# MSV-back.net
KiCad netlist of a schematic drawn in EAGLE
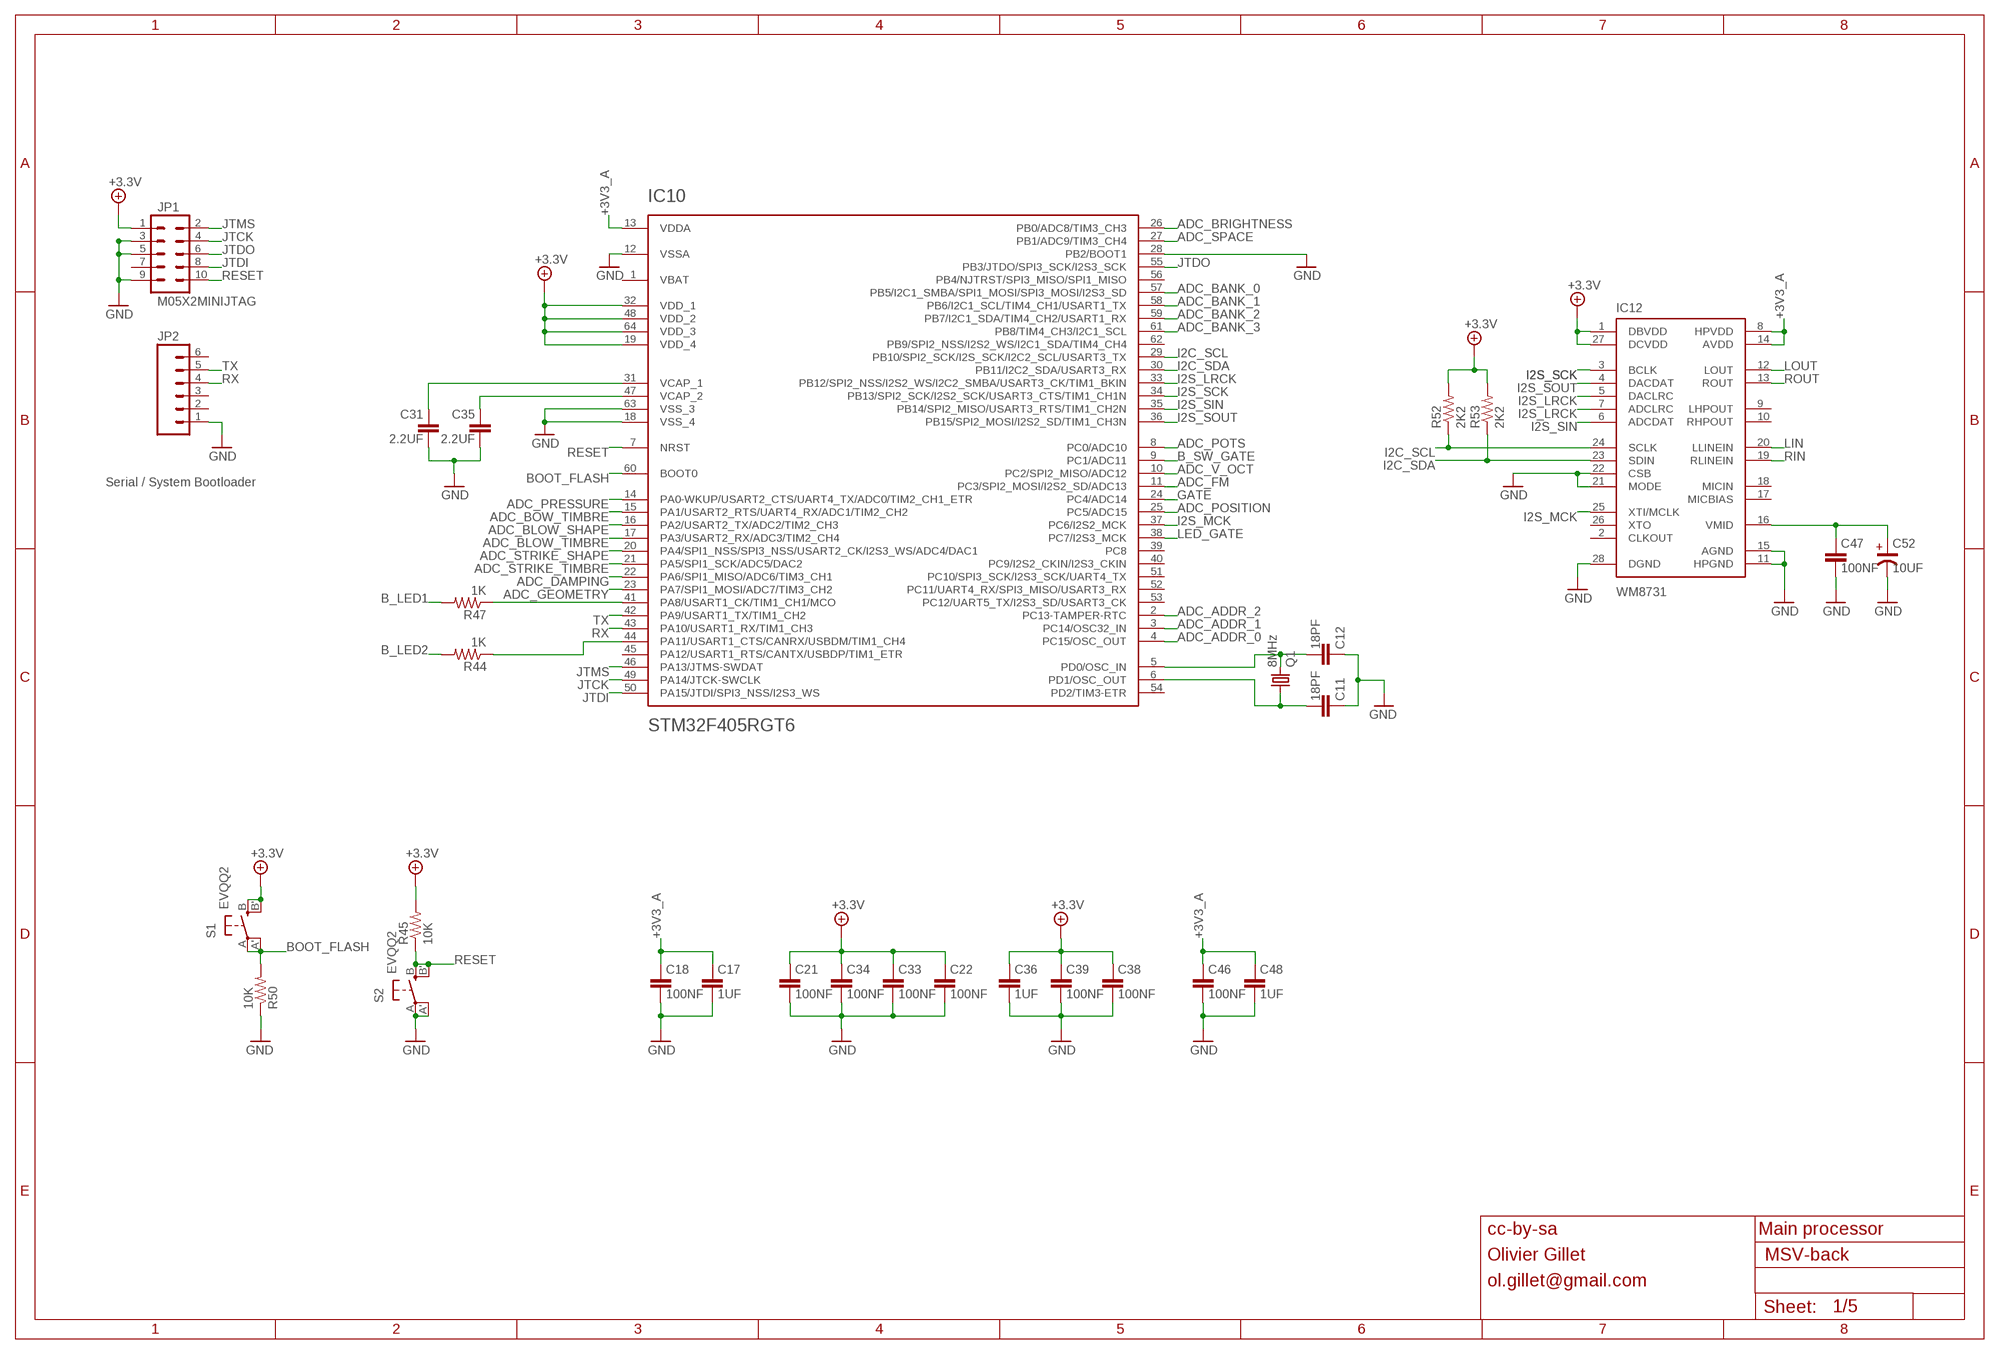
[diagram p0: schematic, sheet 1]
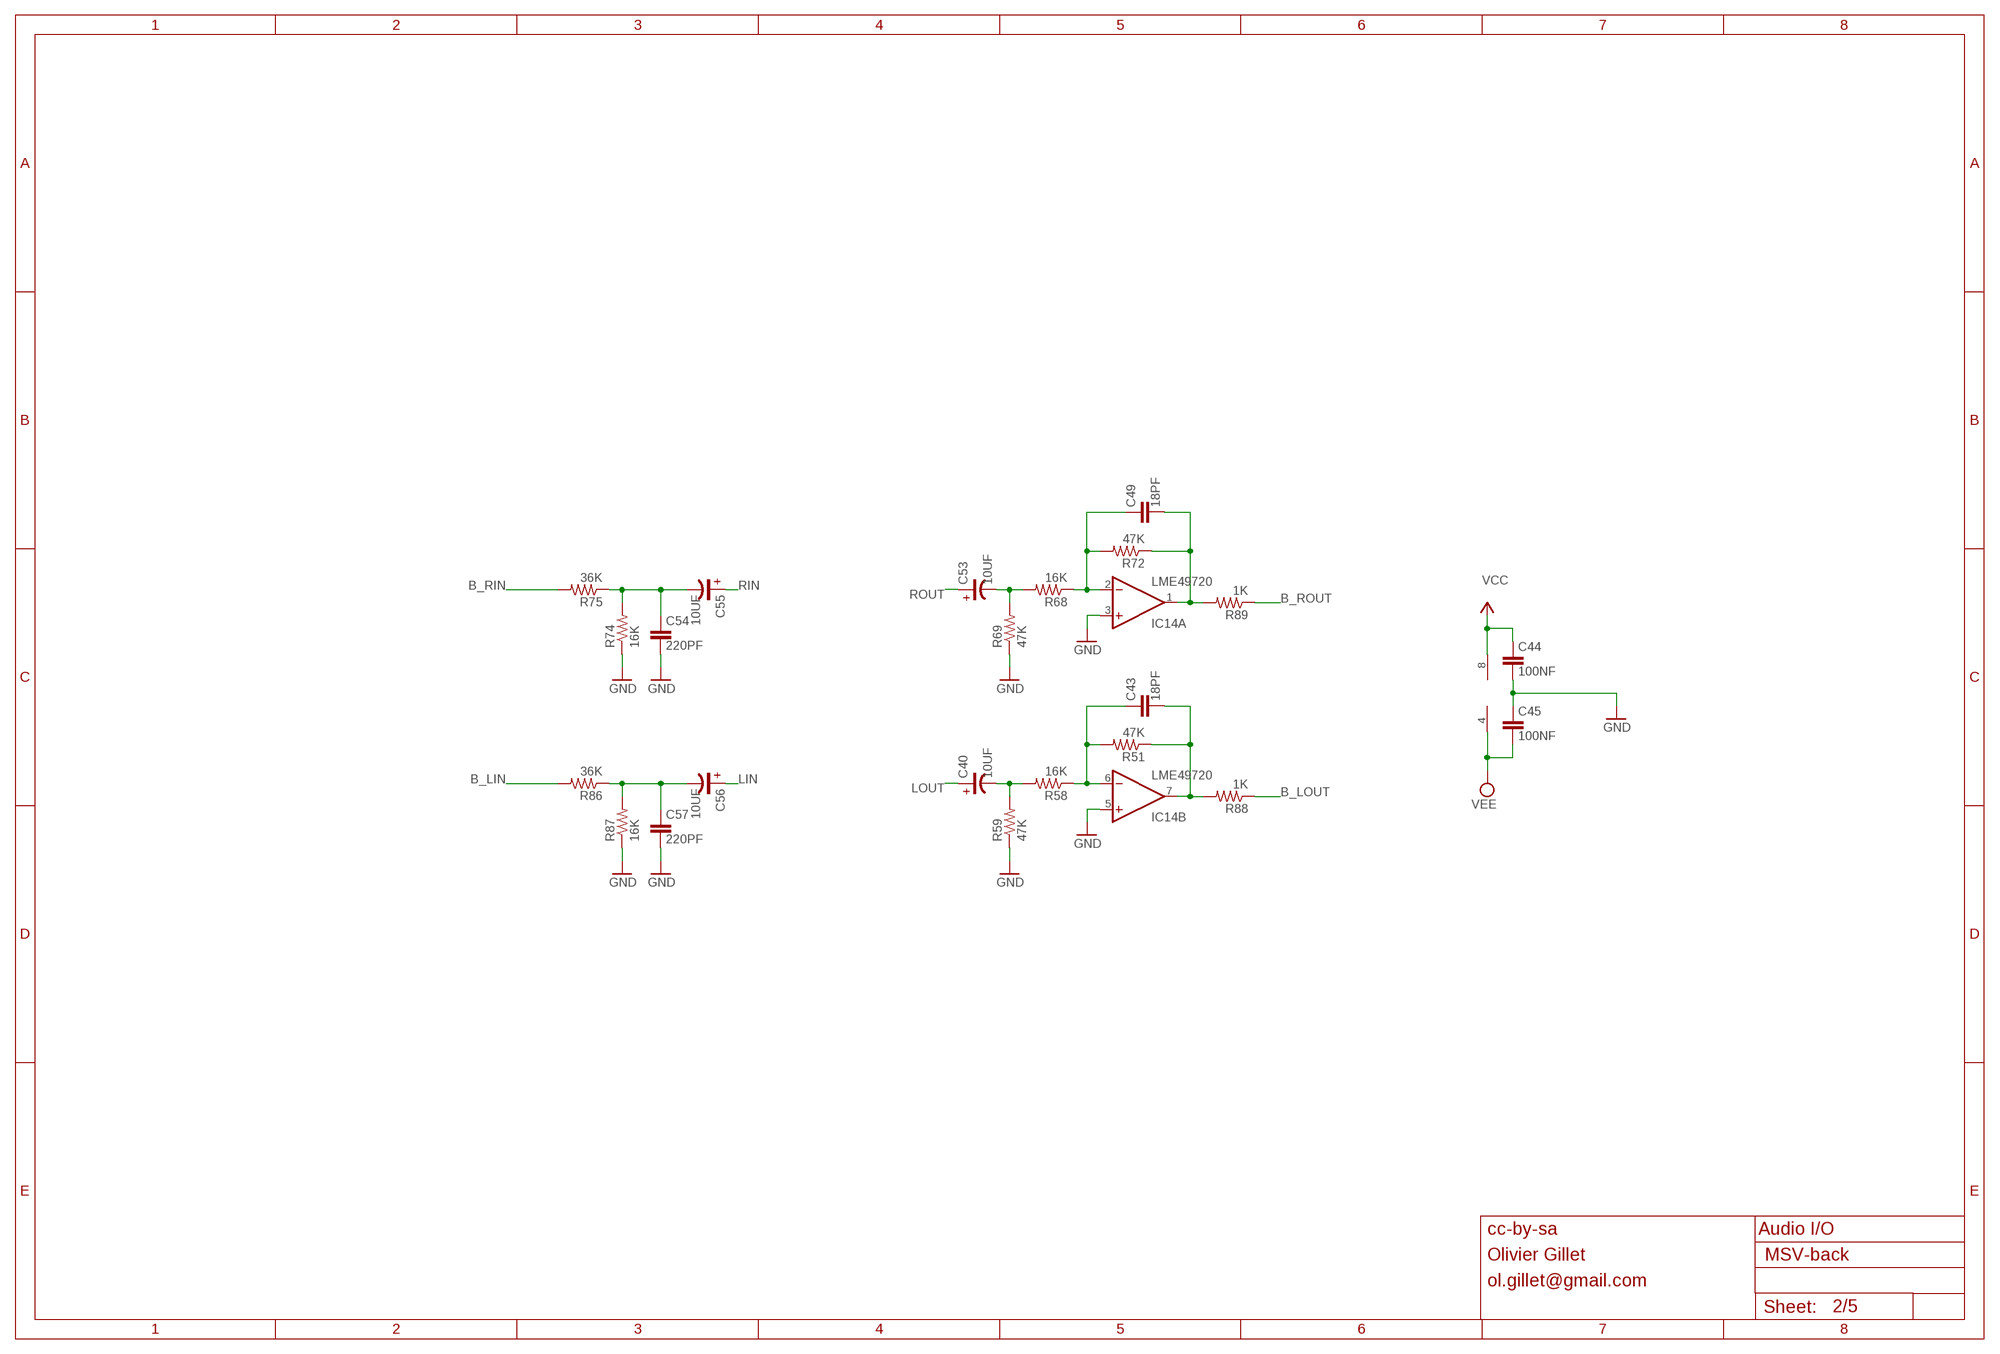
[diagram p1: schematic, sheet 2]
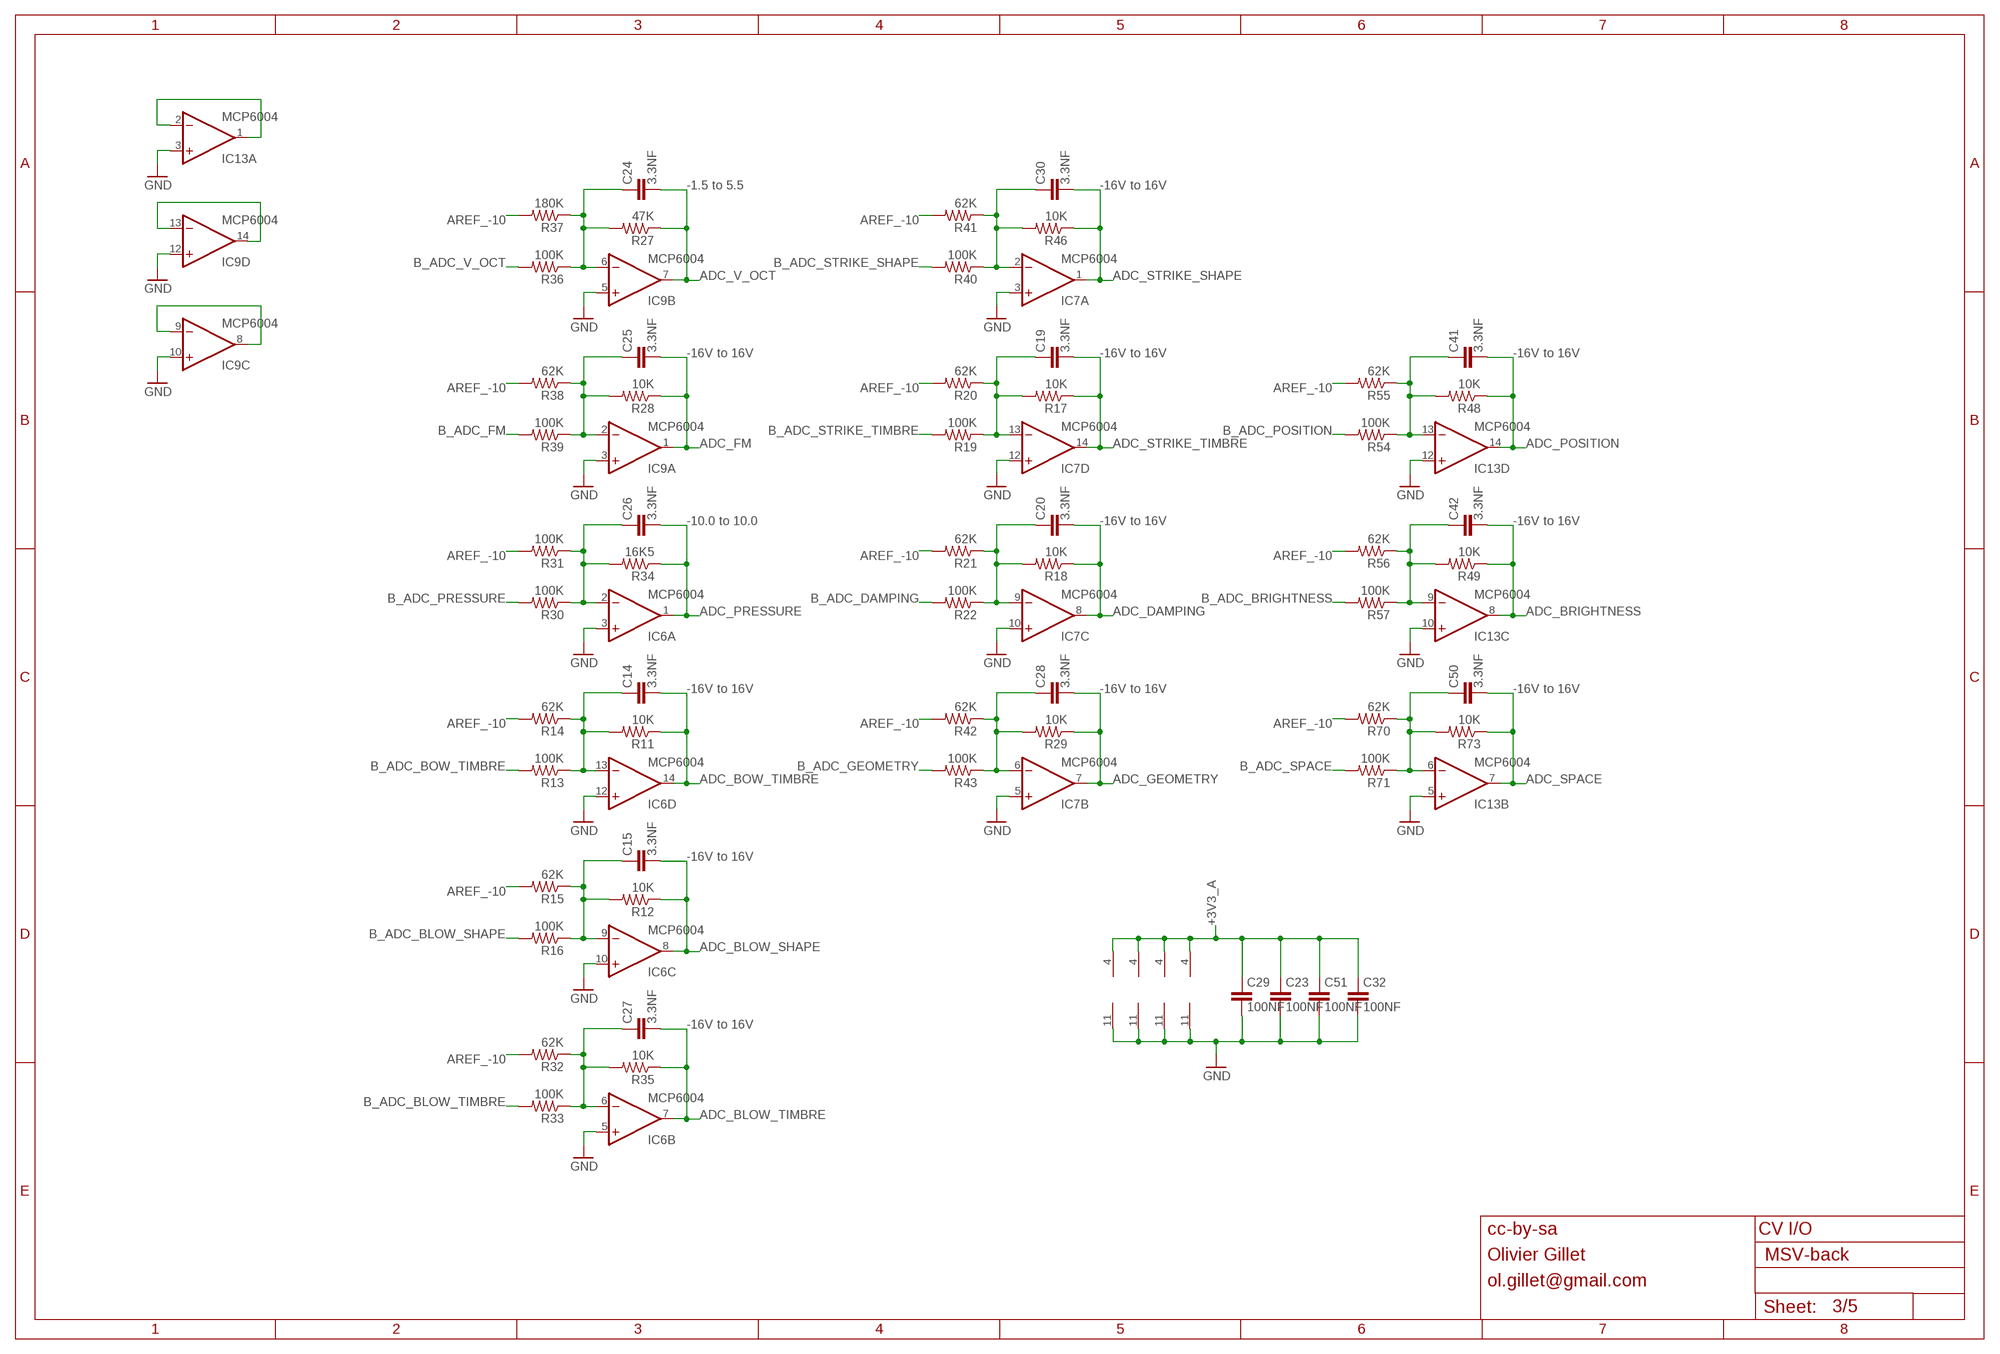
[diagram p2: schematic, sheet 3]
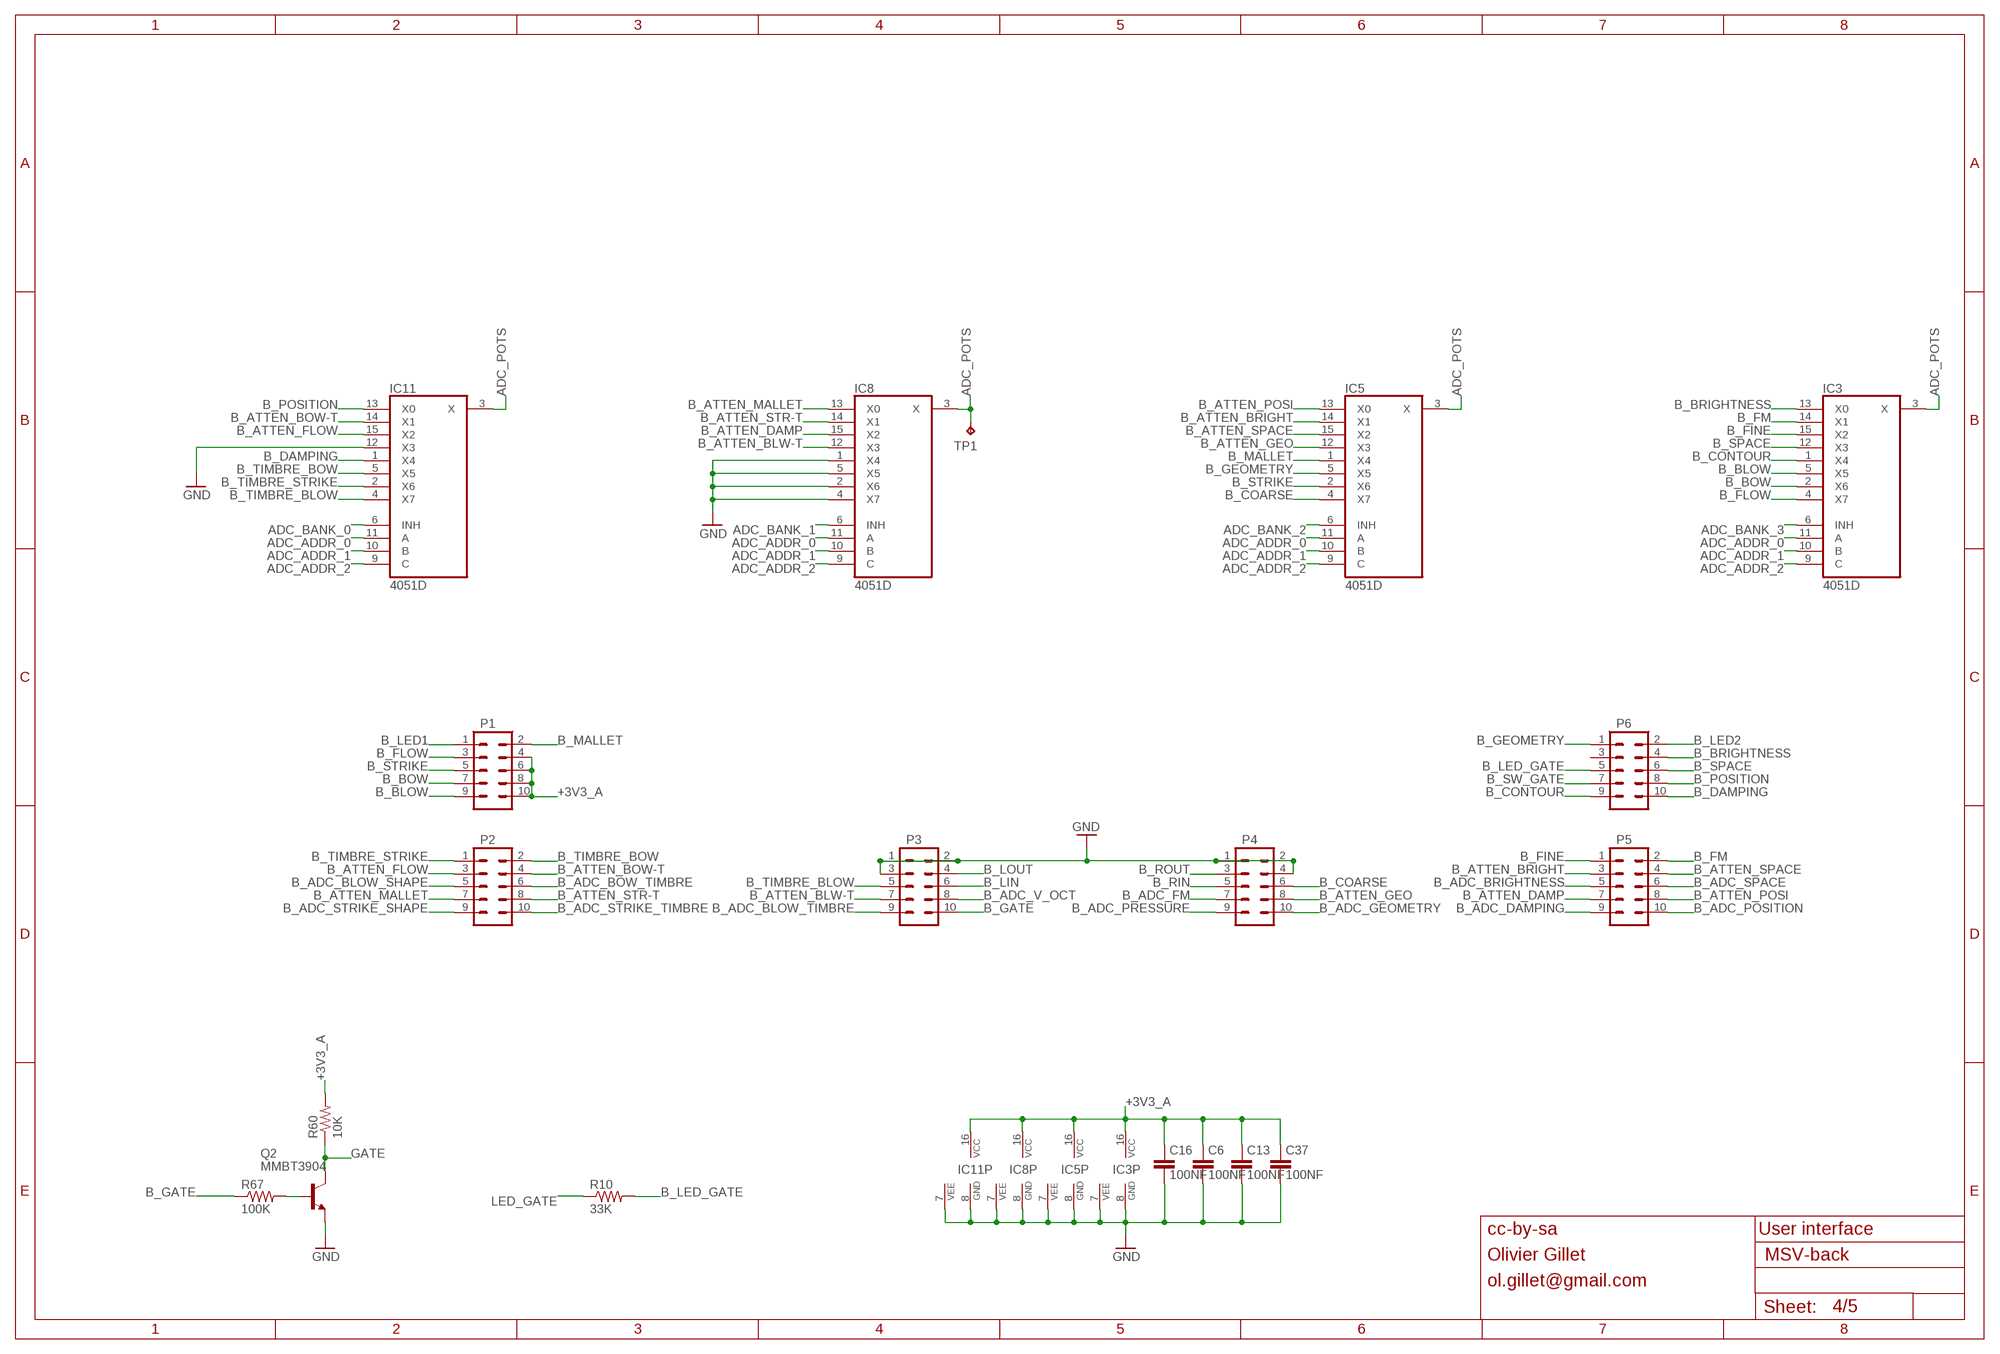
[diagram p3: schematic, sheet 4]
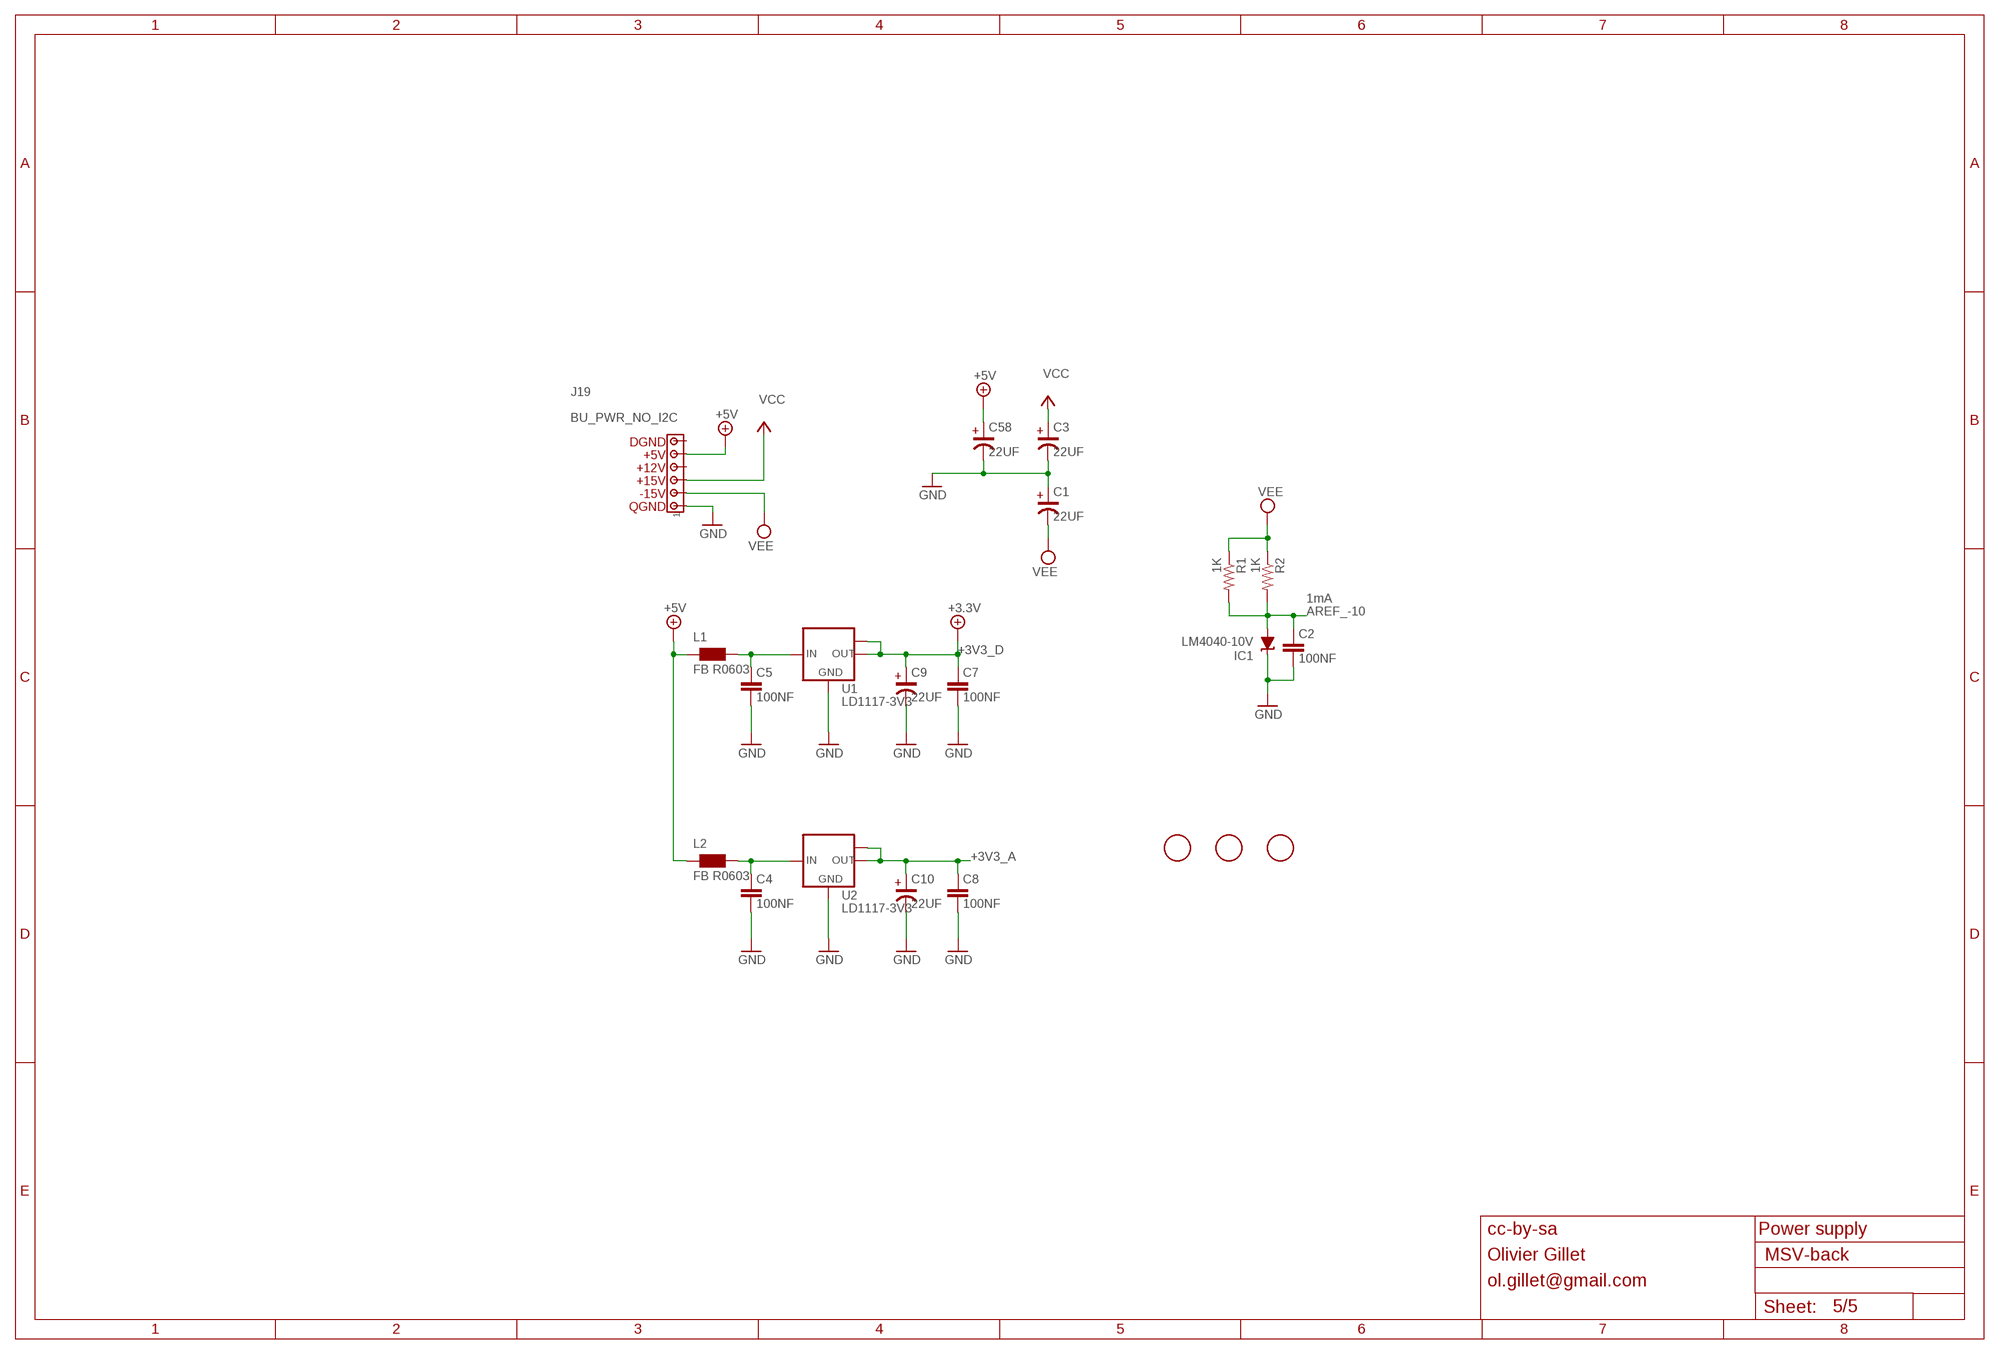
[diagram p4: schematic, sheet 5]

(export (version "E")
  (design (tool "Eeschema 10.0.6"))
  (components
    (comp (ref "C6")
      (value "100NF")
      (footprint "eagle-import:C0603")
      (libsource (lib "eagle-import") (part "C-EUC0603"))
    )
    (comp (ref "C13")
      (value "100NF")
      (footprint "eagle-import:C0603")
      (libsource (lib "eagle-import") (part "C-EUC0603"))
    )
    (comp (ref "C16")
      (value "100NF")
      (footprint "eagle-import:C0603")
      (libsource (lib "eagle-import") (part "C-EUC0603"))
    )
    (comp (ref "C37")
      (value "100NF")
      (footprint "eagle-import:C0603")
      (libsource (lib "eagle-import") (part "C-EUC0603"))
    )
    (comp (ref "IC3")
      (value "4051D")
      (footprint "eagle-import:SO-16")
      (libsource (lib "eagle-import") (part "4051D"))
    )
    (comp (ref "IC5")
      (value "4051D")
      (footprint "eagle-import:SO-16")
      (libsource (lib "eagle-import") (part "4051D"))
    )
    (comp (ref "IC8")
      (value "4051D")
      (footprint "eagle-import:SO-16")
      (libsource (lib "eagle-import") (part "4051D"))
    )
    (comp (ref "IC11")
      (value "4051D")
      (footprint "eagle-import:SO-16")
      (fields (field (name "SPICEPREFIX") "X"))
      (libsource (lib "eagle-import") (part "4051D"))
    )
    (comp (ref "P1")
      (value "M05X2_LOCK_MALE")
      (footprint "eagle-import:2X5_LOCK_MALE")
      (libsource (lib "eagle-import") (part "M05X2_LOCK_MALE"))
    )
    (comp (ref "P2")
      (value "M05X2_LOCK_MALE")
      (footprint "eagle-import:2X5_LOCK_MALE")
      (libsource (lib "eagle-import") (part "M05X2_LOCK_MALE"))
    )
    (comp (ref "P3")
      (value "M05X2_LOCK_MALE")
      (footprint "eagle-import:2X5_LOCK_MALE")
      (libsource (lib "eagle-import") (part "M05X2_LOCK_MALE"))
    )
    (comp (ref "P4")
      (value "M05X2_LOCK_MALE")
      (footprint "eagle-import:2X5_LOCK_MALE")
      (libsource (lib "eagle-import") (part "M05X2_LOCK_MALE"))
    )
    (comp (ref "P5")
      (value "M05X2_LOCK_MALE")
      (footprint "eagle-import:2X5_LOCK_MALE")
      (libsource (lib "eagle-import") (part "M05X2_LOCK_MALE"))
    )
    (comp (ref "P6")
      (value "M05X2_LOCK_MALE")
      (footprint "eagle-import:2X5_LOCK_MALE")
      (libsource (lib "eagle-import") (part "M05X2_LOCK_MALE"))
    )
    (comp (ref "Q2")
      (value "MMBT3904")
      (footprint "eagle-import:SOT23-BEC")
      (libsource (lib "eagle-import") (part "-NPN-SOT23-BECMMBT3904LT1"))
    )
    (comp (ref "R10")
      (value "33K")
      (footprint "eagle-import:R0603")
      (libsource (lib "eagle-import") (part "R-US_R0603"))
    )
    (comp (ref "R60")
      (value "10K")
      (footprint "eagle-import:R0603")
      (libsource (lib "eagle-import") (part "R-US_R0603"))
    )
    (comp (ref "R67")
      (value "100K")
      (footprint "eagle-import:R0603")
      (libsource (lib "eagle-import") (part "R-US_R0603"))
    )
    (comp (ref "TP1")
      (value "TPTP15R")
      (footprint "eagle-import:TP15R")
      (libsource (lib "eagle-import") (part "TPTP15R"))
    )
    (comp (ref "C1")
      (value "22UF")
      (footprint "eagle-import:PANASONIC_C")
      (libsource (lib "eagle-import") (part "C-EU-POL_C"))
    )
    (comp (ref "C2")
      (value "100NF")
      (footprint "eagle-import:C0603")
      (libsource (lib "eagle-import") (part "C-EUC0603"))
    )
    (comp (ref "C3")
      (value "22UF")
      (footprint "eagle-import:PANASONIC_C")
      (libsource (lib "eagle-import") (part "C-EU-POL_C"))
    )
    (comp (ref "C4")
      (value "100NF")
      (footprint "eagle-import:C0603")
      (libsource (lib "eagle-import") (part "C-EUC0603"))
    )
    (comp (ref "C5")
      (value "100NF")
      (footprint "eagle-import:C0603")
      (libsource (lib "eagle-import") (part "C-EUC0603"))
    )
    (comp (ref "C7")
      (value "100NF")
      (footprint "eagle-import:C0603")
      (libsource (lib "eagle-import") (part "C-EUC0603"))
    )
    (comp (ref "C8")
      (value "100NF")
      (footprint "eagle-import:C0603")
      (libsource (lib "eagle-import") (part "C-EUC0603"))
    )
    (comp (ref "C9")
      (value "22UF")
      (footprint "eagle-import:PANASONIC_C")
      (libsource (lib "eagle-import") (part "C-EU-POL_C"))
    )
    (comp (ref "C10")
      (value "22UF")
      (footprint "eagle-import:PANASONIC_C")
      (libsource (lib "eagle-import") (part "C-EU-POL_C"))
    )
    (comp (ref "C58")
      (value "22UF")
      (footprint "eagle-import:PANASONIC_C")
      (libsource (lib "eagle-import") (part "C-EU-POL_C"))
    )
    (comp (ref "FD1")
      (value "FIDUCIAL")
      (footprint "eagle-import:FIDUCIAL_1MM")
      (libsource (lib "eagle-import") (part "FIDUCIAL"))
    )
    (comp (ref "FD2")
      (value "FIDUCIAL")
      (footprint "eagle-import:FIDUCIAL_1MM")
      (libsource (lib "eagle-import") (part "FIDUCIAL"))
    )
    (comp (ref "FD3")
      (value "FIDUCIAL")
      (footprint "eagle-import:FIDUCIAL_1MM")
      (libsource (lib "eagle-import") (part "FIDUCIAL"))
    )
    (comp (ref "IC1")
      (value "LM4040-10V")
      (footprint "eagle-import:DBZ_R-PDSO-G3")
      (fields (field (name "MPN") "LM4041A12IDBZR"))
      (libsource (lib "eagle-import") (part "LM4040-10VDBZA12"))
    )
    (comp (ref "J19")
      (value "BU_PWR_NO_I2C")
      (footprint "eagle-import:MTA_156")
      (libsource (lib "eagle-import") (part "BU_PWR_NO_I2C"))
    )
    (comp (ref "L1")
      (value "FB R0603")
      (footprint "eagle-import:WUERTH-ELEKTRONIK_0603")
      (fields (field (name "MPN") "MI0603J601R-10"))
      (libsource (lib "eagle-import") (part "FERRITE_BEAD_0603"))
    )
    (comp (ref "L2")
      (value "FB R0603")
      (footprint "eagle-import:WUERTH-ELEKTRONIK_0603")
      (fields (field (name "MPN") "MI0603J601R-10"))
      (libsource (lib "eagle-import") (part "FERRITE_BEAD_0603"))
    )
    (comp (ref "R1")
      (value "1K")
      (footprint "eagle-import:R0603")
      (libsource (lib "eagle-import") (part "R-US_R0603"))
    )
    (comp (ref "R2")
      (value "1K")
      (footprint "eagle-import:R0603")
      (libsource (lib "eagle-import") (part "R-US_R0603"))
    )
    (comp (ref "U1")
      (value "LD1117-3V3")
      (footprint "eagle-import:SOT223")
      (fields (field (name "MPN") "LD1117S33CTR"))
      (libsource (lib "eagle-import") (part "LD1117-3V3"))
    )
    (comp (ref "U2")
      (value "LD1117-3V3")
      (footprint "eagle-import:SOT223")
      (fields (field (name "MPN") "LD1117S33CTR"))
      (libsource (lib "eagle-import") (part "LD1117-3V3"))
    )
    (comp (ref "C11")
      (value "18PF")
      (footprint "eagle-import:C0603")
      (libsource (lib "eagle-import") (part "C-EUC0603"))
    )
    (comp (ref "C12")
      (value "18PF")
      (footprint "eagle-import:C0603")
      (libsource (lib "eagle-import") (part "C-EUC0603"))
    )
    (comp (ref "C17")
      (value "1UF")
      (footprint "eagle-import:C0603")
      (libsource (lib "eagle-import") (part "C-EUC0603"))
    )
    (comp (ref "C18")
      (value "100NF")
      (footprint "eagle-import:C0603")
      (libsource (lib "eagle-import") (part "C-EUC0603"))
    )
    (comp (ref "C21")
      (value "100NF")
      (footprint "eagle-import:C0603")
      (libsource (lib "eagle-import") (part "C-EUC0603"))
    )
    (comp (ref "C22")
      (value "100NF")
      (footprint "eagle-import:C0603")
      (libsource (lib "eagle-import") (part "C-EUC0603"))
    )
    (comp (ref "C31")
      (value "2.2UF")
      (footprint "eagle-import:C0603")
      (libsource (lib "eagle-import") (part "C-EUC0603"))
    )
    (comp (ref "C33")
      (value "100NF")
      (footprint "eagle-import:C0603")
      (libsource (lib "eagle-import") (part "C-EUC0603"))
    )
    (comp (ref "C34")
      (value "100NF")
      (footprint "eagle-import:C0603")
      (libsource (lib "eagle-import") (part "C-EUC0603"))
    )
    (comp (ref "C35")
      (value "2.2UF")
      (footprint "eagle-import:C0603")
      (libsource (lib "eagle-import") (part "C-EUC0603"))
    )
    (comp (ref "C36")
      (value "1UF")
      (footprint "eagle-import:C0603")
      (libsource (lib "eagle-import") (part "C-EUC0603"))
    )
    (comp (ref "C38")
      (value "100NF")
      (footprint "eagle-import:C0603")
      (libsource (lib "eagle-import") (part "C-EUC0603"))
    )
    (comp (ref "C39")
      (value "100NF")
      (footprint "eagle-import:C0603")
      (libsource (lib "eagle-import") (part "C-EUC0603"))
    )
    (comp (ref "C46")
      (value "100NF")
      (footprint "eagle-import:C0603")
      (libsource (lib "eagle-import") (part "C-EUC0603"))
    )
    (comp (ref "C47")
      (value "100NF")
      (footprint "eagle-import:C0603")
      (libsource (lib "eagle-import") (part "C-EUC0603"))
    )
    (comp (ref "C48")
      (value "1UF")
      (footprint "eagle-import:C0603")
      (libsource (lib "eagle-import") (part "C-EUC0603"))
    )
    (comp (ref "C52")
      (value "10UF")
      (footprint "eagle-import:PANASONIC_B")
      (libsource (lib "eagle-import") (part "C-EU-POL_B"))
    )
    (comp (ref "IC10")
      (value "STM32F405RGT6")
      (footprint "eagle-import:TQFP-10X10-64")
      (fields (field (name "MPN") "empty"))
      (libsource (lib "eagle-import") (part "STM32F20X"))
    )
    (comp (ref "IC12")
      (value "WM8731")
      (footprint "eagle-import:SSOP-28")
      (fields (field (name "MPN") "WM8731SEDS/RV"))
      (libsource (lib "eagle-import") (part "WM8731"))
    )
    (comp (ref "JP1")
      (value "M05X2MINIJTAG")
      (footprint "eagle-import:2X5-1.27")
      (fields (field (name "MPN") "20021111-00010T4LF"))
      (libsource (lib "eagle-import") (part "M05X2MINIJTAG"))
    )
    (comp (ref "JP2")
      (value "M06_SQUARE")
      (footprint "eagle-import:1X06_SQUARE")
      (libsource (lib "eagle-import") (part "M06_SQUARE"))
    )
    (comp (ref "Q1")
      (value "8MHz")
      (footprint "eagle-import:HC49UP")
      (libsource (lib "eagle-import") (part "CRYSTALHC49UP"))
    )
    (comp (ref "R44")
      (value "1K")
      (footprint "eagle-import:R0603")
      (libsource (lib "eagle-import") (part "R-US_R0603"))
    )
    (comp (ref "R45")
      (value "10K")
      (footprint "eagle-import:R0603")
      (libsource (lib "eagle-import") (part "R-US_R0603"))
    )
    (comp (ref "R47")
      (value "1K")
      (footprint "eagle-import:R0603")
      (libsource (lib "eagle-import") (part "R-US_R0603"))
    )
    (comp (ref "R50")
      (value "10K")
      (footprint "eagle-import:R0603")
      (libsource (lib "eagle-import") (part "R-US_R0603"))
    )
    (comp (ref "R52")
      (value "2K2")
      (footprint "eagle-import:R0603")
      (libsource (lib "eagle-import") (part "R-US_R0603"))
    )
    (comp (ref "R53")
      (value "2K2")
      (footprint "eagle-import:R0603")
      (libsource (lib "eagle-import") (part "R-US_R0603"))
    )
    (comp (ref "S1")
      (value "EVQQ2")
      (footprint "eagle-import:EVQ-Q2")
      (libsource (lib "eagle-import") (part "EVQQ2"))
    )
    (comp (ref "S2")
      (value "EVQQ2")
      (footprint "eagle-import:EVQ-Q2")
      (libsource (lib "eagle-import") (part "EVQQ2"))
    )
    (comp (ref "C40")
      (value "10UF")
      (footprint "eagle-import:PANASONIC_B")
      (libsource (lib "eagle-import") (part "C-EU-POL_B"))
    )
    (comp (ref "C43")
      (value "18PF")
      (footprint "eagle-import:C0603")
      (libsource (lib "eagle-import") (part "C-EUC0603"))
    )
    (comp (ref "C44")
      (value "100NF")
      (footprint "eagle-import:C0603")
      (libsource (lib "eagle-import") (part "C-EUC0603"))
    )
    (comp (ref "C45")
      (value "100NF")
      (footprint "eagle-import:C0603")
      (libsource (lib "eagle-import") (part "C-EUC0603"))
    )
    (comp (ref "C49")
      (value "18PF")
      (footprint "eagle-import:C0603")
      (libsource (lib "eagle-import") (part "C-EUC0603"))
    )
    (comp (ref "C53")
      (value "10UF")
      (footprint "eagle-import:PANASONIC_B")
      (libsource (lib "eagle-import") (part "C-EU-POL_B"))
    )
    (comp (ref "C54")
      (value "220PF")
      (footprint "eagle-import:C0603")
      (libsource (lib "eagle-import") (part "C-EUC0603"))
    )
    (comp (ref "C55")
      (value "10UF")
      (footprint "eagle-import:PANASONIC_B")
      (libsource (lib "eagle-import") (part "C-EU-POL_B"))
    )
    (comp (ref "C56")
      (value "10UF")
      (footprint "eagle-import:PANASONIC_B")
      (libsource (lib "eagle-import") (part "C-EU-POL_B"))
    )
    (comp (ref "C57")
      (value "220PF")
      (footprint "eagle-import:C0603")
      (libsource (lib "eagle-import") (part "C-EUC0603"))
    )
    (comp (ref "IC14")
      (value "LME49720")
      (footprint "eagle-import:TSSOP-8")
      (fields (field (name "MPN") "TL072CPWR"))
      (libsource (lib "eagle-import") (part "TL072_TSSOP-8"))
    )
    (comp (ref "R51")
      (value "47K")
      (footprint "eagle-import:R0603")
      (libsource (lib "eagle-import") (part "R-US_R0603"))
    )
    (comp (ref "R58")
      (value "16K")
      (footprint "eagle-import:R0603")
      (libsource (lib "eagle-import") (part "R-US_R0603"))
    )
    (comp (ref "R59")
      (value "47K")
      (footprint "eagle-import:R0603")
      (libsource (lib "eagle-import") (part "R-US_R0603"))
    )
    (comp (ref "R68")
      (value "16K")
      (footprint "eagle-import:R0603")
      (libsource (lib "eagle-import") (part "R-US_R0603"))
    )
    (comp (ref "R69")
      (value "47K")
      (footprint "eagle-import:R0603")
      (libsource (lib "eagle-import") (part "R-US_R0603"))
    )
    (comp (ref "R72")
      (value "47K")
      (footprint "eagle-import:R0603")
      (libsource (lib "eagle-import") (part "R-US_R0603"))
    )
    (comp (ref "R74")
      (value "16K")
      (footprint "eagle-import:R0603")
      (libsource (lib "eagle-import") (part "R-US_R0603"))
    )
    (comp (ref "R75")
      (value "36K")
      (footprint "eagle-import:R0603")
      (libsource (lib "eagle-import") (part "R-US_R0603"))
    )
    (comp (ref "R86")
      (value "36K")
      (footprint "eagle-import:R0603")
      (libsource (lib "eagle-import") (part "R-US_R0603"))
    )
    (comp (ref "R87")
      (value "16K")
      (footprint "eagle-import:R0603")
      (libsource (lib "eagle-import") (part "R-US_R0603"))
    )
    (comp (ref "R88")
      (value "1K")
      (footprint "eagle-import:R0603")
      (libsource (lib "eagle-import") (part "R-US_R0603"))
    )
    (comp (ref "R89")
      (value "1K")
      (footprint "eagle-import:R0603")
      (libsource (lib "eagle-import") (part "R-US_R0603"))
    )
    (comp (ref "C14")
      (value "3.3NF")
      (footprint "eagle-import:C0603")
      (libsource (lib "eagle-import") (part "C-EUC0603"))
    )
    (comp (ref "C15")
      (value "3.3NF")
      (footprint "eagle-import:C0603")
      (libsource (lib "eagle-import") (part "C-EUC0603"))
    )
    (comp (ref "C19")
      (value "3.3NF")
      (footprint "eagle-import:C0603")
      (libsource (lib "eagle-import") (part "C-EUC0603"))
    )
    (comp (ref "C20")
      (value "3.3NF")
      (footprint "eagle-import:C0603")
      (libsource (lib "eagle-import") (part "C-EUC0603"))
    )
    (comp (ref "C23")
      (value "100NF")
      (footprint "eagle-import:C0603")
      (libsource (lib "eagle-import") (part "C-EUC0603"))
    )
    (comp (ref "C24")
      (value "3.3NF")
      (footprint "eagle-import:C0603")
      (libsource (lib "eagle-import") (part "C-EUC0603"))
    )
    (comp (ref "C25")
      (value "3.3NF")
      (footprint "eagle-import:C0603")
      (libsource (lib "eagle-import") (part "C-EUC0603"))
    )
    (comp (ref "C26")
      (value "3.3NF")
      (footprint "eagle-import:C0603")
      (libsource (lib "eagle-import") (part "C-EUC0603"))
    )
    (comp (ref "C27")
      (value "3.3NF")
      (footprint "eagle-import:C0603")
      (libsource (lib "eagle-import") (part "C-EUC0603"))
    )
    (comp (ref "C28")
      (value "3.3NF")
      (footprint "eagle-import:C0603")
      (libsource (lib "eagle-import") (part "C-EUC0603"))
    )
    (comp (ref "C29")
      (value "100NF")
      (footprint "eagle-import:C0603")
      (libsource (lib "eagle-import") (part "C-EUC0603"))
    )
    (comp (ref "C30")
      (value "3.3NF")
      (footprint "eagle-import:C0603")
      (libsource (lib "eagle-import") (part "C-EUC0603"))
    )
    (comp (ref "C32")
      (value "100NF")
      (footprint "eagle-import:C0603")
      (libsource (lib "eagle-import") (part "C-EUC0603"))
    )
    (comp (ref "C41")
      (value "3.3NF")
      (footprint "eagle-import:C0603")
      (libsource (lib "eagle-import") (part "C-EUC0603"))
    )
    (comp (ref "C42")
      (value "3.3NF")
      (footprint "eagle-import:C0603")
      (libsource (lib "eagle-import") (part "C-EUC0603"))
    )
    (comp (ref "C50")
      (value "3.3NF")
      (footprint "eagle-import:C0603")
      (libsource (lib "eagle-import") (part "C-EUC0603"))
    )
    (comp (ref "C51")
      (value "100NF")
      (footprint "eagle-import:C0603")
      (libsource (lib "eagle-import") (part "C-EUC0603"))
    )
    (comp (ref "IC6")
      (value "MCP6004")
      (footprint "eagle-import:TSSOP-14")
      (fields (field (name "MPN") "MCP6004T-E/ST"))
      (libsource (lib "eagle-import") (part "MCP6004_TSSOP-14"))
    )
    (comp (ref "IC7")
      (value "MCP6004")
      (footprint "eagle-import:TSSOP-14")
      (fields (field (name "MPN") "MCP6004T-E/ST"))
      (libsource (lib "eagle-import") (part "MCP6004_TSSOP-14"))
    )
    (comp (ref "IC9")
      (value "MCP6004")
      (footprint "eagle-import:TSSOP-14")
      (fields (field (name "MPN") "MCP6004T-E/ST"))
      (libsource (lib "eagle-import") (part "MCP6004_TSSOP-14"))
    )
    (comp (ref "IC13")
      (value "MCP6004")
      (footprint "eagle-import:TSSOP-14")
      (fields (field (name "MPN") "MCP6004T-E/ST"))
      (libsource (lib "eagle-import") (part "MCP6004_TSSOP-14"))
    )
    (comp (ref "R11")
      (value "10K")
      (footprint "eagle-import:R0603")
      (libsource (lib "eagle-import") (part "R-US_R0603"))
    )
    (comp (ref "R12")
      (value "10K")
      (footprint "eagle-import:R0603")
      (libsource (lib "eagle-import") (part "R-US_R0603"))
    )
    (comp (ref "R13")
      (value "100K")
      (footprint "eagle-import:R0603")
      (libsource (lib "eagle-import") (part "R-US_R0603"))
    )
    (comp (ref "R14")
      (value "62K")
      (footprint "eagle-import:R0603")
      (libsource (lib "eagle-import") (part "R-US_R0603"))
    )
    (comp (ref "R15")
      (value "62K")
      (footprint "eagle-import:R0603")
      (libsource (lib "eagle-import") (part "R-US_R0603"))
    )
    (comp (ref "R16")
      (value "100K")
      (footprint "eagle-import:R0603")
      (libsource (lib "eagle-import") (part "R-US_R0603"))
    )
    (comp (ref "R17")
      (value "10K")
      (footprint "eagle-import:R0603")
      (libsource (lib "eagle-import") (part "R-US_R0603"))
    )
    (comp (ref "R18")
      (value "10K")
      (footprint "eagle-import:R0603")
      (libsource (lib "eagle-import") (part "R-US_R0603"))
    )
    (comp (ref "R19")
      (value "100K")
      (footprint "eagle-import:R0603")
      (libsource (lib "eagle-import") (part "R-US_R0603"))
    )
    (comp (ref "R20")
      (value "62K")
      (footprint "eagle-import:R0603")
      (libsource (lib "eagle-import") (part "R-US_R0603"))
    )
    (comp (ref "R21")
      (value "62K")
      (footprint "eagle-import:R0603")
      (libsource (lib "eagle-import") (part "R-US_R0603"))
    )
    (comp (ref "R22")
      (value "100K")
      (footprint "eagle-import:R0603")
      (libsource (lib "eagle-import") (part "R-US_R0603"))
    )
    (comp (ref "R27")
      (value "47K")
      (footprint "eagle-import:R0603")
      (libsource (lib "eagle-import") (part "R-US_R0603"))
    )
    (comp (ref "R28")
      (value "10K")
      (footprint "eagle-import:R0603")
      (libsource (lib "eagle-import") (part "R-US_R0603"))
    )
    (comp (ref "R29")
      (value "10K")
      (footprint "eagle-import:R0603")
      (libsource (lib "eagle-import") (part "R-US_R0603"))
    )
    (comp (ref "R30")
      (value "100K")
      (footprint "eagle-import:R0603")
      (libsource (lib "eagle-import") (part "R-US_R0603"))
    )
    (comp (ref "R31")
      (value "100K")
      (footprint "eagle-import:R0603")
      (libsource (lib "eagle-import") (part "R-US_R0603"))
    )
    (comp (ref "R32")
      (value "62K")
      (footprint "eagle-import:R0603")
      (libsource (lib "eagle-import") (part "R-US_R0603"))
    )
    (comp (ref "R33")
      (value "100K")
      (footprint "eagle-import:R0603")
      (libsource (lib "eagle-import") (part "R-US_R0603"))
    )
    (comp (ref "R34")
      (value "16K5")
      (footprint "eagle-import:R0603")
      (libsource (lib "eagle-import") (part "R-US_R0603"))
    )
    (comp (ref "R35")
      (value "10K")
      (footprint "eagle-import:R0603")
      (libsource (lib "eagle-import") (part "R-US_R0603"))
    )
    (comp (ref "R36")
      (value "100K")
      (footprint "eagle-import:R0603")
      (libsource (lib "eagle-import") (part "R-US_R0603"))
    )
    (comp (ref "R37")
      (value "180K")
      (footprint "eagle-import:R0603")
      (libsource (lib "eagle-import") (part "R-US_R0603"))
    )
    (comp (ref "R38")
      (value "62K")
      (footprint "eagle-import:R0603")
      (libsource (lib "eagle-import") (part "R-US_R0603"))
    )
    (comp (ref "R39")
      (value "100K")
      (footprint "eagle-import:R0603")
      (libsource (lib "eagle-import") (part "R-US_R0603"))
    )
    (comp (ref "R40")
      (value "100K")
      (footprint "eagle-import:R0603")
      (libsource (lib "eagle-import") (part "R-US_R0603"))
    )
    (comp (ref "R41")
      (value "62K")
      (footprint "eagle-import:R0603")
      (libsource (lib "eagle-import") (part "R-US_R0603"))
    )
    (comp (ref "R42")
      (value "62K")
      (footprint "eagle-import:R0603")
      (libsource (lib "eagle-import") (part "R-US_R0603"))
    )
    (comp (ref "R43")
      (value "100K")
      (footprint "eagle-import:R0603")
      (libsource (lib "eagle-import") (part "R-US_R0603"))
    )
    (comp (ref "R46")
      (value "10K")
      (footprint "eagle-import:R0603")
      (libsource (lib "eagle-import") (part "R-US_R0603"))
    )
    (comp (ref "R48")
      (value "10K")
      (footprint "eagle-import:R0603")
      (libsource (lib "eagle-import") (part "R-US_R0603"))
    )
    (comp (ref "R49")
      (value "10K")
      (footprint "eagle-import:R0603")
      (libsource (lib "eagle-import") (part "R-US_R0603"))
    )
    (comp (ref "R54")
      (value "100K")
      (footprint "eagle-import:R0603")
      (libsource (lib "eagle-import") (part "R-US_R0603"))
    )
    (comp (ref "R55")
      (value "62K")
      (footprint "eagle-import:R0603")
      (libsource (lib "eagle-import") (part "R-US_R0603"))
    )
    (comp (ref "R56")
      (value "62K")
      (footprint "eagle-import:R0603")
      (libsource (lib "eagle-import") (part "R-US_R0603"))
    )
    (comp (ref "R57")
      (value "100K")
      (footprint "eagle-import:R0603")
      (libsource (lib "eagle-import") (part "R-US_R0603"))
    )
    (comp (ref "R70")
      (value "62K")
      (footprint "eagle-import:R0603")
      (libsource (lib "eagle-import") (part "R-US_R0603"))
    )
    (comp (ref "R71")
      (value "100K")
      (footprint "eagle-import:R0603")
      (libsource (lib "eagle-import") (part "R-US_R0603"))
    )
    (comp (ref "R73")
      (value "10K")
      (footprint "eagle-import:R0603")
      (libsource (lib "eagle-import") (part "R-US_R0603"))
    )
  )
  (nets
    (net (code "1") (name "+3V3_A") (class "Default")
      (node (ref "C10") (pin "+") (pinfunction "POS_+") (pintype "passive"))
      (node (ref "C13") (pin "1") (pinfunction "1_1") (pintype "passive"))
      (node (ref "C16") (pin "1") (pinfunction "1_1") (pintype "passive"))
      (node (ref "C17") (pin "1") (pinfunction "1_1") (pintype "passive"))
      (node (ref "C18") (pin "1") (pinfunction "1_1") (pintype "passive"))
      (node (ref "C23") (pin "1") (pinfunction "1_1") (pintype "passive"))
      (node (ref "C29") (pin "1") (pinfunction "1_1") (pintype "passive"))
      (node (ref "C32") (pin "1") (pinfunction "1_1") (pintype "passive"))
      (node (ref "C37") (pin "1") (pinfunction "1_1") (pintype "passive"))
      (node (ref "C46") (pin "1") (pinfunction "1_1") (pintype "passive"))
      (node (ref "C48") (pin "1") (pinfunction "1_1") (pintype "passive"))
      (node (ref "C51") (pin "1") (pinfunction "1_1") (pintype "passive"))
      (node (ref "C6") (pin "1") (pinfunction "1_1") (pintype "passive"))
      (node (ref "C8") (pin "1") (pinfunction "1_1") (pintype "passive"))
      (node (ref "IC10") (pin "13") (pinfunction "VDDA_13") (pintype "power_in"))
      (node (ref "IC11") (pin "16") (pinfunction "VCC_16") (pintype "power_in"))
      (node (ref "IC12") (pin "14") (pinfunction "AVDD_14") (pintype "bidirectional"))
      (node (ref "IC12") (pin "8") (pinfunction "HPVDD_8") (pintype "bidirectional"))
      (node (ref "IC13") (pin "4") (pinfunction "V+_4") (pintype "power_in"))
      (node (ref "IC3") (pin "16") (pinfunction "VCC_16") (pintype "power_in"))
      (node (ref "IC5") (pin "16") (pinfunction "VCC_16") (pintype "power_in"))
      (node (ref "IC6") (pin "4") (pinfunction "V+_4") (pintype "power_in"))
      (node (ref "IC7") (pin "4") (pinfunction "V+_4") (pintype "power_in"))
      (node (ref "IC8") (pin "16") (pinfunction "VCC_16") (pintype "power_in"))
      (node (ref "IC9") (pin "4") (pinfunction "V+_4") (pintype "power_in"))
      (node (ref "P1") (pin "10") (pinfunction "10_10") (pintype "passive"))
      (node (ref "P1") (pin "4") (pinfunction "4_4") (pintype "passive"))
      (node (ref "P1") (pin "6") (pinfunction "6_6") (pintype "passive"))
      (node (ref "P1") (pin "8") (pinfunction "8_8") (pintype "passive"))
      (node (ref "R60") (pin "2") (pinfunction "2_2") (pintype "passive"))
      (node (ref "U2") (pin "2") (pinfunction "OUT_2") (pintype "passive"))
      (node (ref "U2") (pin "TAB") (pinfunction "OUT1_TAB") (pintype "passive"))
    )
    (net (code "2") (name "+3V3_D") (class "Default")
      (node (ref "C21") (pin "1") (pinfunction "1_1") (pintype "passive"))
      (node (ref "C22") (pin "1") (pinfunction "1_1") (pintype "passive"))
      (node (ref "C33") (pin "1") (pinfunction "1_1") (pintype "passive"))
      (node (ref "C34") (pin "1") (pinfunction "1_1") (pintype "passive"))
      (node (ref "C36") (pin "1") (pinfunction "1_1") (pintype "passive"))
      (node (ref "C38") (pin "1") (pinfunction "1_1") (pintype "passive"))
      (node (ref "C39") (pin "1") (pinfunction "1_1") (pintype "passive"))
      (node (ref "C7") (pin "1") (pinfunction "1_1") (pintype "passive"))
      (node (ref "C9") (pin "+") (pinfunction "POS_+") (pintype "passive"))
      (node (ref "IC10") (pin "19") (pinfunction "VDD_4_19") (pintype "power_in"))
      (node (ref "IC10") (pin "32") (pinfunction "VDD_1_32") (pintype "power_in"))
      (node (ref "IC10") (pin "48") (pinfunction "VDD_2_48") (pintype "power_in"))
      (node (ref "IC10") (pin "64") (pinfunction "VDD_3_64") (pintype "power_in"))
      (node (ref "IC12") (pin "1") (pinfunction "DBVDD_1") (pintype "bidirectional"))
      (node (ref "IC12") (pin "27") (pinfunction "DCVDD_27") (pintype "bidirectional"))
      (node (ref "JP1") (pin "1") (pinfunction "1_1") (pintype "passive"))
      (node (ref "R45") (pin "2") (pinfunction "2_2") (pintype "passive"))
      (node (ref "R52") (pin "2") (pinfunction "2_2") (pintype "passive"))
      (node (ref "R53") (pin "2") (pinfunction "2_2") (pintype "passive"))
      (node (ref "S1") (pin "B") (pinfunction "S_B") (pintype "passive"))
      (node (ref "S1") (pin "B'") (pinfunction "S1_B'") (pintype "passive"))
      (node (ref "U1") (pin "2") (pinfunction "OUT_2") (pintype "passive"))
      (node (ref "U1") (pin "TAB") (pinfunction "OUT1_TAB") (pintype "passive"))
    )
    (net (code "3") (name "+5V") (class "Default")
      (node (ref "C58") (pin "+") (pinfunction "POS_+") (pintype "passive"))
      (node (ref "J19") (pin "5") (pinfunction "5_5") (pintype "passive"))
      (node (ref "L1") (pin "1") (pinfunction "1_1") (pintype "passive"))
      (node (ref "L2") (pin "1") (pinfunction "1_1") (pintype "passive"))
    )
    (net (code "4") (name "ADC_ADDR_0") (class "Default")
      (node (ref "IC10") (pin "4") (pinfunction "PC15/OSC_OUT_4") (pintype "bidirectional"))
      (node (ref "IC11") (pin "11") (pinfunction "A_11") (pintype "input"))
      (node (ref "IC3") (pin "11") (pinfunction "A_11") (pintype "input"))
      (node (ref "IC5") (pin "11") (pinfunction "A_11") (pintype "input"))
      (node (ref "IC8") (pin "11") (pinfunction "A_11") (pintype "input"))
    )
    (net (code "5") (name "ADC_ADDR_1") (class "Default")
      (node (ref "IC10") (pin "3") (pinfunction "PC14/OSC32_IN_3") (pintype "bidirectional"))
      (node (ref "IC11") (pin "10") (pinfunction "B_10") (pintype "input"))
      (node (ref "IC3") (pin "10") (pinfunction "B_10") (pintype "input"))
      (node (ref "IC5") (pin "10") (pinfunction "B_10") (pintype "input"))
      (node (ref "IC8") (pin "10") (pinfunction "B_10") (pintype "input"))
    )
    (net (code "6") (name "ADC_ADDR_2") (class "Default")
      (node (ref "IC10") (pin "2") (pinfunction "PC13-TAMPER-RTC_2") (pintype "bidirectional"))
      (node (ref "IC11") (pin "9") (pinfunction "C_9") (pintype "input"))
      (node (ref "IC3") (pin "9") (pinfunction "C_9") (pintype "input"))
      (node (ref "IC5") (pin "9") (pinfunction "C_9") (pintype "input"))
      (node (ref "IC8") (pin "9") (pinfunction "C_9") (pintype "input"))
    )
    (net (code "7") (name "ADC_BANK_0") (class "Default")
      (node (ref "IC10") (pin "57") (pinfunction "PB5/I2C1_SMBA/SPI1_MOSI/SPI3_MOSI/I2S3_SD_57") (pintype "bidirectional"))
      (node (ref "IC11") (pin "6") (pinfunction "INH_6") (pintype "input"))
    )
    (net (code "8") (name "ADC_BANK_1") (class "Default")
      (node (ref "IC10") (pin "58") (pinfunction "PB6/I2C1_SCL/TIM4_CH1/USART1_TX_58") (pintype "bidirectional"))
      (node (ref "IC8") (pin "6") (pinfunction "INH_6") (pintype "input"))
    )
    (net (code "9") (name "ADC_BANK_2") (class "Default")
      (node (ref "IC10") (pin "59") (pinfunction "PB7/I2C1_SDA/TIM4_CH2/USART1_RX_59") (pintype "bidirectional"))
      (node (ref "IC5") (pin "6") (pinfunction "INH_6") (pintype "input"))
    )
    (net (code "10") (name "ADC_BANK_3") (class "Default")
      (node (ref "IC10") (pin "61") (pinfunction "PB8/TIM4_CH3/I2C1_SCL_61") (pintype "bidirectional"))
      (node (ref "IC3") (pin "6") (pinfunction "INH_6") (pintype "input"))
    )
    (net (code "11") (name "ADC_BLOW_SHAPE") (class "Default")
      (node (ref "C15") (pin "2") (pinfunction "2_2") (pintype "passive"))
      (node (ref "IC10") (pin "16") (pinfunction "PA2/USART2_TX/ADC2/TIM2_CH3_16") (pintype "bidirectional"))
      (node (ref "IC6") (pin "8") (pinfunction "OUT_8") (pintype "output"))
      (node (ref "R12") (pin "1") (pinfunction "1_1") (pintype "passive"))
    )
    (net (code "12") (name "ADC_BLOW_TIMBRE") (class "Default")
      (node (ref "C27") (pin "2") (pinfunction "2_2") (pintype "passive"))
      (node (ref "IC10") (pin "17") (pinfunction "PA3/USART2_RX/ADC3/TIM2_CH4_17") (pintype "bidirectional"))
      (node (ref "IC6") (pin "7") (pinfunction "OUT_7") (pintype "output"))
      (node (ref "R35") (pin "1") (pinfunction "1_1") (pintype "passive"))
    )
    (net (code "13") (name "ADC_BOW_TIMBRE") (class "Default")
      (node (ref "C14") (pin "2") (pinfunction "2_2") (pintype "passive"))
      (node (ref "IC10") (pin "15") (pinfunction "PA1/USART2_RTS/UART4_RX/ADC1/TIM2_CH2_15") (pintype "bidirectional"))
      (node (ref "IC6") (pin "14") (pinfunction "OUT_14") (pintype "output"))
      (node (ref "R11") (pin "1") (pinfunction "1_1") (pintype "passive"))
    )
    (net (code "14") (name "ADC_BRIGHTNESS") (class "Default")
      (node (ref "C42") (pin "2") (pinfunction "2_2") (pintype "passive"))
      (node (ref "IC10") (pin "26") (pinfunction "PB0/ADC8/TIM3_CH3_26") (pintype "bidirectional"))
      (node (ref "IC13") (pin "8") (pinfunction "OUT_8") (pintype "output"))
      (node (ref "R49") (pin "1") (pinfunction "1_1") (pintype "passive"))
    )
    (net (code "15") (name "ADC_DAMPING") (class "Default")
      (node (ref "C20") (pin "2") (pinfunction "2_2") (pintype "passive"))
      (node (ref "IC10") (pin "22") (pinfunction "PA6/SPI1_MISO/ADC6/TIM3_CH1_22") (pintype "bidirectional"))
      (node (ref "IC7") (pin "8") (pinfunction "OUT_8") (pintype "output"))
      (node (ref "R18") (pin "1") (pinfunction "1_1") (pintype "passive"))
    )
    (net (code "16") (name "ADC_FM") (class "Default")
      (node (ref "C25") (pin "2") (pinfunction "2_2") (pintype "passive"))
      (node (ref "IC10") (pin "11") (pinfunction "PC3/SPI2_MOSI/I2S2_SD/ADC13_11") (pintype "bidirectional"))
      (node (ref "IC9") (pin "1") (pinfunction "OUT_1") (pintype "output"))
      (node (ref "R28") (pin "1") (pinfunction "1_1") (pintype "passive"))
    )
    (net (code "17") (name "ADC_GEOMETRY") (class "Default")
      (node (ref "C28") (pin "2") (pinfunction "2_2") (pintype "passive"))
      (node (ref "IC10") (pin "23") (pinfunction "PA7/SPI1_MOSI/ADC7/TIM3_CH2_23") (pintype "bidirectional"))
      (node (ref "IC7") (pin "7") (pinfunction "OUT_7") (pintype "output"))
      (node (ref "R29") (pin "1") (pinfunction "1_1") (pintype "passive"))
    )
    (net (code "18") (name "ADC_POSITION") (class "Default")
      (node (ref "C41") (pin "2") (pinfunction "2_2") (pintype "passive"))
      (node (ref "IC10") (pin "25") (pinfunction "PC5/ADC15_25") (pintype "bidirectional"))
      (node (ref "IC13") (pin "14") (pinfunction "OUT_14") (pintype "output"))
      (node (ref "R48") (pin "1") (pinfunction "1_1") (pintype "passive"))
    )
    (net (code "19") (name "ADC_POTS") (class "Default")
      (node (ref "IC10") (pin "8") (pinfunction "PC0/ADC10_8") (pintype "bidirectional"))
      (node (ref "IC11") (pin "3") (pinfunction "X_3") (pintype "bidirectional"))
      (node (ref "IC3") (pin "3") (pinfunction "X_3") (pintype "bidirectional"))
      (node (ref "IC5") (pin "3") (pinfunction "X_3") (pintype "bidirectional"))
      (node (ref "IC8") (pin "3") (pinfunction "X_3") (pintype "bidirectional"))
      (node (ref "TP1") (pin "TP") (pinfunction "TP_TP") (pintype "input"))
    )
    (net (code "20") (name "ADC_PRESSURE") (class "Default")
      (node (ref "C26") (pin "2") (pinfunction "2_2") (pintype "passive"))
      (node (ref "IC10") (pin "14") (pinfunction "PA0-WKUP/USART2_CTS/UART4_TX/ADC0/TIM2_CH1_ETR_14") (pintype "bidirectional"))
      (node (ref "IC6") (pin "1") (pinfunction "OUT_1") (pintype "output"))
      (node (ref "R34") (pin "1") (pinfunction "1_1") (pintype "passive"))
    )
    (net (code "21") (name "ADC_SPACE") (class "Default")
      (node (ref "C50") (pin "2") (pinfunction "2_2") (pintype "passive"))
      (node (ref "IC10") (pin "27") (pinfunction "PB1/ADC9/TIM3_CH4_27") (pintype "bidirectional"))
      (node (ref "IC13") (pin "7") (pinfunction "OUT_7") (pintype "output"))
      (node (ref "R73") (pin "1") (pinfunction "1_1") (pintype "passive"))
    )
    (net (code "22") (name "ADC_STRIKE_SHAPE") (class "Default")
      (node (ref "C30") (pin "2") (pinfunction "2_2") (pintype "passive"))
      (node (ref "IC10") (pin "20") (pinfunction "PA4/SPI1_NSS/SPI3_NSS/USART2_CK/I2S3_WS/ADC4/DAC1_20") (pintype "bidirectional"))
      (node (ref "IC7") (pin "1") (pinfunction "OUT_1") (pintype "output"))
      (node (ref "R46") (pin "1") (pinfunction "1_1") (pintype "passive"))
    )
    (net (code "23") (name "ADC_STRIKE_TIMBRE") (class "Default")
      (node (ref "C19") (pin "2") (pinfunction "2_2") (pintype "passive"))
      (node (ref "IC10") (pin "21") (pinfunction "PA5/SPI1_SCK/ADC5/DAC2_21") (pintype "bidirectional"))
      (node (ref "IC7") (pin "14") (pinfunction "OUT_14") (pintype "output"))
      (node (ref "R17") (pin "1") (pinfunction "1_1") (pintype "passive"))
    )
    (net (code "24") (name "ADC_V_OCT") (class "Default")
      (node (ref "C24") (pin "2") (pinfunction "2_2") (pintype "passive"))
      (node (ref "IC10") (pin "10") (pinfunction "PC2/SPI2_MISO/ADC12_10") (pintype "bidirectional"))
      (node (ref "IC9") (pin "7") (pinfunction "OUT_7") (pintype "output"))
      (node (ref "R27") (pin "1") (pinfunction "1_1") (pintype "passive"))
    )
    (net (code "25") (name "AREF_-10") (class "Default")
      (node (ref "C2") (pin "1") (pinfunction "1_1") (pintype "passive"))
      (node (ref "IC1") (pin "2") (pinfunction "A_2") (pintype "passive"))
      (node (ref "R1") (pin "2") (pinfunction "2_2") (pintype "passive"))
      (node (ref "R14") (pin "2") (pinfunction "2_2") (pintype "passive"))
      (node (ref "R15") (pin "2") (pinfunction "2_2") (pintype "passive"))
      (node (ref "R2") (pin "2") (pinfunction "2_2") (pintype "passive"))
      (node (ref "R20") (pin "2") (pinfunction "2_2") (pintype "passive"))
      (node (ref "R21") (pin "2") (pinfunction "2_2") (pintype "passive"))
      (node (ref "R31") (pin "2") (pinfunction "2_2") (pintype "passive"))
      (node (ref "R32") (pin "2") (pinfunction "2_2") (pintype "passive"))
      (node (ref "R37") (pin "2") (pinfunction "2_2") (pintype "passive"))
      (node (ref "R38") (pin "2") (pinfunction "2_2") (pintype "passive"))
      (node (ref "R41") (pin "2") (pinfunction "2_2") (pintype "passive"))
      (node (ref "R42") (pin "2") (pinfunction "2_2") (pintype "passive"))
      (node (ref "R55") (pin "2") (pinfunction "2_2") (pintype "passive"))
      (node (ref "R56") (pin "2") (pinfunction "2_2") (pintype "passive"))
      (node (ref "R70") (pin "2") (pinfunction "2_2") (pintype "passive"))
    )
    (net (code "26") (name "BOOT_FLASH") (class "Default")
      (node (ref "IC10") (pin "60") (pinfunction "BOOT0_60") (pintype "bidirectional"))
      (node (ref "R50") (pin "2") (pinfunction "2_2") (pintype "passive"))
      (node (ref "S1") (pin "A") (pinfunction "P_A") (pintype "passive"))
      (node (ref "S1") (pin "A'") (pinfunction "P1_A'") (pintype "passive"))
    )
    (net (code "27") (name "B_ADC_BLOW_SHAPE") (class "Default")
      (node (ref "P2") (pin "5") (pinfunction "5_5") (pintype "passive"))
      (node (ref "R16") (pin "2") (pinfunction "2_2") (pintype "passive"))
    )
    (net (code "28") (name "B_ADC_BLOW_TIMBRE") (class "Default")
      (node (ref "P3") (pin "9") (pinfunction "9_9") (pintype "passive"))
      (node (ref "R33") (pin "2") (pinfunction "2_2") (pintype "passive"))
    )
    (net (code "29") (name "B_ADC_BOW_TIMBRE") (class "Default")
      (node (ref "P2") (pin "6") (pinfunction "6_6") (pintype "passive"))
      (node (ref "R13") (pin "2") (pinfunction "2_2") (pintype "passive"))
    )
    (net (code "30") (name "B_ADC_BRIGHTNESS") (class "Default")
      (node (ref "P5") (pin "5") (pinfunction "5_5") (pintype "passive"))
      (node (ref "R57") (pin "2") (pinfunction "2_2") (pintype "passive"))
    )
    (net (code "31") (name "B_ADC_DAMPING") (class "Default")
      (node (ref "P5") (pin "9") (pinfunction "9_9") (pintype "passive"))
      (node (ref "R22") (pin "2") (pinfunction "2_2") (pintype "passive"))
    )
    (net (code "32") (name "B_ADC_FM") (class "Default")
      (node (ref "P4") (pin "7") (pinfunction "7_7") (pintype "passive"))
      (node (ref "R39") (pin "2") (pinfunction "2_2") (pintype "passive"))
    )
    (net (code "33") (name "B_ADC_GEOMETRY") (class "Default")
      (node (ref "P4") (pin "10") (pinfunction "10_10") (pintype "passive"))
      (node (ref "R43") (pin "2") (pinfunction "2_2") (pintype "passive"))
    )
    (net (code "34") (name "B_ADC_POSITION") (class "Default")
      (node (ref "P5") (pin "10") (pinfunction "10_10") (pintype "passive"))
      (node (ref "R54") (pin "2") (pinfunction "2_2") (pintype "passive"))
    )
    (net (code "35") (name "B_ADC_PRESSURE") (class "Default")
      (node (ref "P4") (pin "9") (pinfunction "9_9") (pintype "passive"))
      (node (ref "R30") (pin "2") (pinfunction "2_2") (pintype "passive"))
    )
    (net (code "36") (name "B_ADC_SPACE") (class "Default")
      (node (ref "P5") (pin "6") (pinfunction "6_6") (pintype "passive"))
      (node (ref "R71") (pin "2") (pinfunction "2_2") (pintype "passive"))
    )
    (net (code "37") (name "B_ADC_STRIKE_SHAPE") (class "Default")
      (node (ref "P2") (pin "9") (pinfunction "9_9") (pintype "passive"))
      (node (ref "R40") (pin "2") (pinfunction "2_2") (pintype "passive"))
    )
    (net (code "38") (name "B_ADC_STRIKE_TIMBRE") (class "Default")
      (node (ref "P2") (pin "10") (pinfunction "10_10") (pintype "passive"))
      (node (ref "R19") (pin "2") (pinfunction "2_2") (pintype "passive"))
    )
    (net (code "39") (name "B_ADC_V_OCT") (class "Default")
      (node (ref "P3") (pin "8") (pinfunction "8_8") (pintype "passive"))
      (node (ref "R36") (pin "2") (pinfunction "2_2") (pintype "passive"))
    )
    (net (code "40") (name "B_ATTEN_BLW-T") (class "Default")
      (node (ref "IC8") (pin "12") (pinfunction "X3_12") (pintype "bidirectional"))
      (node (ref "P3") (pin "7") (pinfunction "7_7") (pintype "passive"))
    )
    (net (code "41") (name "B_ATTEN_BOW-T") (class "Default")
      (node (ref "IC11") (pin "14") (pinfunction "X1_14") (pintype "bidirectional"))
      (node (ref "P2") (pin "4") (pinfunction "4_4") (pintype "passive"))
    )
    (net (code "42") (name "B_ATTEN_BRIGHT") (class "Default")
      (node (ref "IC5") (pin "14") (pinfunction "X1_14") (pintype "bidirectional"))
      (node (ref "P5") (pin "3") (pinfunction "3_3") (pintype "passive"))
    )
    (net (code "43") (name "B_ATTEN_DAMP") (class "Default")
      (node (ref "IC8") (pin "15") (pinfunction "X2_15") (pintype "bidirectional"))
      (node (ref "P5") (pin "7") (pinfunction "7_7") (pintype "passive"))
    )
    (net (code "44") (name "B_ATTEN_FLOW") (class "Default")
      (node (ref "IC11") (pin "15") (pinfunction "X2_15") (pintype "bidirectional"))
      (node (ref "P2") (pin "3") (pinfunction "3_3") (pintype "passive"))
    )
    (net (code "45") (name "B_ATTEN_GEO") (class "Default")
      (node (ref "IC5") (pin "12") (pinfunction "X3_12") (pintype "bidirectional"))
      (node (ref "P4") (pin "8") (pinfunction "8_8") (pintype "passive"))
    )
    (net (code "46") (name "B_ATTEN_MALLET") (class "Default")
      (node (ref "IC8") (pin "13") (pinfunction "X0_13") (pintype "bidirectional"))
      (node (ref "P2") (pin "7") (pinfunction "7_7") (pintype "passive"))
    )
    (net (code "47") (name "B_ATTEN_POSI") (class "Default")
      (node (ref "IC5") (pin "13") (pinfunction "X0_13") (pintype "bidirectional"))
      (node (ref "P5") (pin "8") (pinfunction "8_8") (pintype "passive"))
    )
    (net (code "48") (name "B_ATTEN_SPACE") (class "Default")
      (node (ref "IC5") (pin "15") (pinfunction "X2_15") (pintype "bidirectional"))
      (node (ref "P5") (pin "4") (pinfunction "4_4") (pintype "passive"))
    )
    (net (code "49") (name "B_ATTEN_STR-T") (class "Default")
      (node (ref "IC8") (pin "14") (pinfunction "X1_14") (pintype "bidirectional"))
      (node (ref "P2") (pin "8") (pinfunction "8_8") (pintype "passive"))
    )
    (net (code "50") (name "B_BLOW") (class "Default")
      (node (ref "IC3") (pin "5") (pinfunction "X5_5") (pintype "bidirectional"))
      (node (ref "P1") (pin "9") (pinfunction "9_9") (pintype "passive"))
    )
    (net (code "51") (name "B_BOW") (class "Default")
      (node (ref "IC3") (pin "2") (pinfunction "X6_2") (pintype "bidirectional"))
      (node (ref "P1") (pin "7") (pinfunction "7_7") (pintype "passive"))
    )
    (net (code "52") (name "B_BRIGHTNESS") (class "Default")
      (node (ref "IC3") (pin "13") (pinfunction "X0_13") (pintype "bidirectional"))
      (node (ref "P6") (pin "4") (pinfunction "4_4") (pintype "passive"))
    )
    (net (code "53") (name "B_COARSE") (class "Default")
      (node (ref "IC5") (pin "4") (pinfunction "X7_4") (pintype "bidirectional"))
      (node (ref "P4") (pin "6") (pinfunction "6_6") (pintype "passive"))
    )
    (net (code "54") (name "B_CONTOUR") (class "Default")
      (node (ref "IC3") (pin "1") (pinfunction "X4_1") (pintype "bidirectional"))
      (node (ref "P6") (pin "9") (pinfunction "9_9") (pintype "passive"))
    )
    (net (code "55") (name "B_DAMPING") (class "Default")
      (node (ref "IC11") (pin "1") (pinfunction "X4_1") (pintype "bidirectional"))
      (node (ref "P6") (pin "10") (pinfunction "10_10") (pintype "passive"))
    )
    (net (code "56") (name "B_FINE") (class "Default")
      (node (ref "IC3") (pin "15") (pinfunction "X2_15") (pintype "bidirectional"))
      (node (ref "P5") (pin "1") (pinfunction "1_1") (pintype "passive"))
    )
    (net (code "57") (name "B_FLOW") (class "Default")
      (node (ref "IC3") (pin "4") (pinfunction "X7_4") (pintype "bidirectional"))
      (node (ref "P1") (pin "3") (pinfunction "3_3") (pintype "passive"))
    )
    (net (code "58") (name "B_FM") (class "Default")
      (node (ref "IC3") (pin "14") (pinfunction "X1_14") (pintype "bidirectional"))
      (node (ref "P5") (pin "2") (pinfunction "2_2") (pintype "passive"))
    )
    (net (code "59") (name "B_GATE") (class "Default")
      (node (ref "P3") (pin "10") (pinfunction "10_10") (pintype "passive"))
      (node (ref "R67") (pin "1") (pinfunction "1_1") (pintype "passive"))
    )
    (net (code "60") (name "B_GEOMETRY") (class "Default")
      (node (ref "IC5") (pin "5") (pinfunction "X5_5") (pintype "bidirectional"))
      (node (ref "P6") (pin "1") (pinfunction "1_1") (pintype "passive"))
    )
    (net (code "61") (name "B_LED1") (class "Default")
      (node (ref "P1") (pin "1") (pinfunction "1_1") (pintype "passive"))
      (node (ref "R47") (pin "2") (pinfunction "2_2") (pintype "passive"))
    )
    (net (code "62") (name "B_LED2") (class "Default")
      (node (ref "P6") (pin "2") (pinfunction "2_2") (pintype "passive"))
      (node (ref "R44") (pin "2") (pinfunction "2_2") (pintype "passive"))
    )
    (net (code "63") (name "B_LED_GATE") (class "Default")
      (node (ref "P6") (pin "5") (pinfunction "5_5") (pintype "passive"))
      (node (ref "R10") (pin "2") (pinfunction "2_2") (pintype "passive"))
    )
    (net (code "64") (name "B_LIN") (class "Default")
      (node (ref "P3") (pin "6") (pinfunction "6_6") (pintype "passive"))
      (node (ref "R86") (pin "2") (pinfunction "2_2") (pintype "passive"))
    )
    (net (code "65") (name "B_LOUT") (class "Default")
      (node (ref "P3") (pin "4") (pinfunction "4_4") (pintype "passive"))
      (node (ref "R88") (pin "1") (pinfunction "1_1") (pintype "passive"))
    )
    (net (code "66") (name "B_MALLET") (class "Default")
      (node (ref "IC5") (pin "1") (pinfunction "X4_1") (pintype "bidirectional"))
      (node (ref "P1") (pin "2") (pinfunction "2_2") (pintype "passive"))
    )
    (net (code "67") (name "B_POSITION") (class "Default")
      (node (ref "IC11") (pin "13") (pinfunction "X0_13") (pintype "bidirectional"))
      (node (ref "P6") (pin "8") (pinfunction "8_8") (pintype "passive"))
    )
    (net (code "68") (name "B_RIN") (class "Default")
      (node (ref "P4") (pin "5") (pinfunction "5_5") (pintype "passive"))
      (node (ref "R75") (pin "2") (pinfunction "2_2") (pintype "passive"))
    )
    (net (code "69") (name "B_ROUT") (class "Default")
      (node (ref "P4") (pin "3") (pinfunction "3_3") (pintype "passive"))
      (node (ref "R89") (pin "1") (pinfunction "1_1") (pintype "passive"))
    )
    (net (code "70") (name "B_SPACE") (class "Default")
      (node (ref "IC3") (pin "12") (pinfunction "X3_12") (pintype "bidirectional"))
      (node (ref "P6") (pin "6") (pinfunction "6_6") (pintype "passive"))
    )
    (net (code "71") (name "B_STRIKE") (class "Default")
      (node (ref "IC5") (pin "2") (pinfunction "X6_2") (pintype "bidirectional"))
      (node (ref "P1") (pin "5") (pinfunction "5_5") (pintype "passive"))
    )
    (net (code "72") (name "B_SW_GATE") (class "Default")
      (node (ref "IC10") (pin "9") (pinfunction "PC1/ADC11_9") (pintype "bidirectional"))
      (node (ref "P6") (pin "7") (pinfunction "7_7") (pintype "passive"))
    )
    (net (code "73") (name "B_TIMBRE_BLOW") (class "Default")
      (node (ref "IC11") (pin "4") (pinfunction "X7_4") (pintype "bidirectional"))
      (node (ref "P3") (pin "5") (pinfunction "5_5") (pintype "passive"))
    )
    (net (code "74") (name "B_TIMBRE_BOW") (class "Default")
      (node (ref "IC11") (pin "5") (pinfunction "X5_5") (pintype "bidirectional"))
      (node (ref "P2") (pin "2") (pinfunction "2_2") (pintype "passive"))
    )
    (net (code "75") (name "B_TIMBRE_STRIKE") (class "Default")
      (node (ref "IC11") (pin "2") (pinfunction "X6_2") (pintype "bidirectional"))
      (node (ref "P2") (pin "1") (pinfunction "1_1") (pintype "passive"))
    )
    (net (code "76") (name "GATE") (class "Default")
      (node (ref "IC10") (pin "24") (pinfunction "PC4/ADC14_24") (pintype "bidirectional"))
      (node (ref "Q2") (pin "C") (pinfunction "C_C") (pintype "passive"))
      (node (ref "R60") (pin "1") (pinfunction "1_1") (pintype "passive"))
    )
    (net (code "77") (name "GND") (class "Default")
      (node (ref "C1") (pin "+") (pinfunction "POS_+") (pintype "passive"))
      (node (ref "C10") (pin "-") (pinfunction "NEG_-") (pintype "passive"))
      (node (ref "C11") (pin "1") (pinfunction "1_1") (pintype "passive"))
      (node (ref "C12") (pin "1") (pinfunction "1_1") (pintype "passive"))
      (node (ref "C13") (pin "2") (pinfunction "2_2") (pintype "passive"))
      (node (ref "C16") (pin "2") (pinfunction "2_2") (pintype "passive"))
      (node (ref "C17") (pin "2") (pinfunction "2_2") (pintype "passive"))
      (node (ref "C18") (pin "2") (pinfunction "2_2") (pintype "passive"))
      (node (ref "C2") (pin "2") (pinfunction "2_2") (pintype "passive"))
      (node (ref "C21") (pin "2") (pinfunction "2_2") (pintype "passive"))
      (node (ref "C22") (pin "2") (pinfunction "2_2") (pintype "passive"))
      (node (ref "C23") (pin "2") (pinfunction "2_2") (pintype "passive"))
      (node (ref "C29") (pin "2") (pinfunction "2_2") (pintype "passive"))
      (node (ref "C3") (pin "-") (pinfunction "NEG_-") (pintype "passive"))
      (node (ref "C31") (pin "2") (pinfunction "2_2") (pintype "passive"))
      (node (ref "C32") (pin "2") (pinfunction "2_2") (pintype "passive"))
      (node (ref "C33") (pin "2") (pinfunction "2_2") (pintype "passive"))
      (node (ref "C34") (pin "2") (pinfunction "2_2") (pintype "passive"))
      (node (ref "C35") (pin "2") (pinfunction "2_2") (pintype "passive"))
      (node (ref "C36") (pin "2") (pinfunction "2_2") (pintype "passive"))
      (node (ref "C37") (pin "2") (pinfunction "2_2") (pintype "passive"))
      (node (ref "C38") (pin "2") (pinfunction "2_2") (pintype "passive"))
      (node (ref "C39") (pin "2") (pinfunction "2_2") (pintype "passive"))
      (node (ref "C4") (pin "2") (pinfunction "2_2") (pintype "passive"))
      (node (ref "C44") (pin "2") (pinfunction "2_2") (pintype "passive"))
      (node (ref "C45") (pin "1") (pinfunction "1_1") (pintype "passive"))
      (node (ref "C46") (pin "2") (pinfunction "2_2") (pintype "passive"))
      (node (ref "C47") (pin "2") (pinfunction "2_2") (pintype "passive"))
      (node (ref "C48") (pin "2") (pinfunction "2_2") (pintype "passive"))
      (node (ref "C5") (pin "2") (pinfunction "2_2") (pintype "passive"))
      (node (ref "C51") (pin "2") (pinfunction "2_2") (pintype "passive"))
      (node (ref "C52") (pin "-") (pinfunction "NEG_-") (pintype "passive"))
      (node (ref "C54") (pin "2") (pinfunction "2_2") (pintype "passive"))
      (node (ref "C57") (pin "2") (pinfunction "2_2") (pintype "passive"))
      (node (ref "C58") (pin "-") (pinfunction "NEG_-") (pintype "passive"))
      (node (ref "C6") (pin "2") (pinfunction "2_2") (pintype "passive"))
      (node (ref "C7") (pin "2") (pinfunction "2_2") (pintype "passive"))
      (node (ref "C8") (pin "2") (pinfunction "2_2") (pintype "passive"))
      (node (ref "C9") (pin "-") (pinfunction "NEG_-") (pintype "passive"))
      (node (ref "IC1") (pin "1") (pinfunction "C_1") (pintype "passive"))
      (node (ref "IC10") (pin "12") (pinfunction "VSSA_12") (pintype "power_in"))
      (node (ref "IC10") (pin "18") (pinfunction "VSS_4_18") (pintype "power_in"))
      (node (ref "IC10") (pin "28") (pinfunction "PB2/BOOT1_28") (pintype "bidirectional"))
      (node (ref "IC10") (pin "63") (pinfunction "VSS_3_63") (pintype "power_in"))
      (node (ref "IC11") (pin "12") (pinfunction "X3_12") (pintype "bidirectional"))
      (node (ref "IC11") (pin "7") (pinfunction "VEE_7") (pintype "power_in"))
      (node (ref "IC11") (pin "8") (pinfunction "GND_8") (pintype "power_in"))
      (node (ref "IC12") (pin "11") (pinfunction "HPGND_11") (pintype "bidirectional"))
      (node (ref "IC12") (pin "15") (pinfunction "AGND_15") (pintype "bidirectional"))
      (node (ref "IC12") (pin "21") (pinfunction "MODE_21") (pintype "bidirectional"))
      (node (ref "IC12") (pin "22") (pinfunction "CSB_22") (pintype "bidirectional"))
      (node (ref "IC12") (pin "28") (pinfunction "DGND_28") (pintype "bidirectional"))
      (node (ref "IC13") (pin "10") (pinfunction "+IN_10") (pintype "input"))
      (node (ref "IC13") (pin "11") (pinfunction "V-_11") (pintype "power_in"))
      (node (ref "IC13") (pin "12") (pinfunction "+IN_12") (pintype "input"))
      (node (ref "IC13") (pin "3") (pinfunction "+IN_3") (pintype "input"))
      (node (ref "IC13") (pin "5") (pinfunction "+IN_5") (pintype "input"))
      (node (ref "IC14") (pin "3") (pinfunction "+IN_3") (pintype "input"))
      (node (ref "IC14") (pin "5") (pinfunction "+IN_5") (pintype "input"))
      (node (ref "IC3") (pin "7") (pinfunction "VEE_7") (pintype "power_in"))
      (node (ref "IC3") (pin "8") (pinfunction "GND_8") (pintype "power_in"))
      (node (ref "IC5") (pin "7") (pinfunction "VEE_7") (pintype "power_in"))
      (node (ref "IC5") (pin "8") (pinfunction "GND_8") (pintype "power_in"))
      (node (ref "IC6") (pin "10") (pinfunction "+IN_10") (pintype "input"))
      (node (ref "IC6") (pin "11") (pinfunction "V-_11") (pintype "power_in"))
      (node (ref "IC6") (pin "12") (pinfunction "+IN_12") (pintype "input"))
      (node (ref "IC6") (pin "3") (pinfunction "+IN_3") (pintype "input"))
      (node (ref "IC6") (pin "5") (pinfunction "+IN_5") (pintype "input"))
      (node (ref "IC7") (pin "10") (pinfunction "+IN_10") (pintype "input"))
      (node (ref "IC7") (pin "11") (pinfunction "V-_11") (pintype "power_in"))
      (node (ref "IC7") (pin "12") (pinfunction "+IN_12") (pintype "input"))
      (node (ref "IC7") (pin "3") (pinfunction "+IN_3") (pintype "input"))
      (node (ref "IC7") (pin "5") (pinfunction "+IN_5") (pintype "input"))
      (node (ref "IC8") (pin "1") (pinfunction "X4_1") (pintype "bidirectional"))
      (node (ref "IC8") (pin "2") (pinfunction "X6_2") (pintype "bidirectional"))
      (node (ref "IC8") (pin "4") (pinfunction "X7_4") (pintype "bidirectional"))
      (node (ref "IC8") (pin "5") (pinfunction "X5_5") (pintype "bidirectional"))
      (node (ref "IC8") (pin "7") (pinfunction "VEE_7") (pintype "power_in"))
      (node (ref "IC8") (pin "8") (pinfunction "GND_8") (pintype "power_in"))
      (node (ref "IC9") (pin "10") (pinfunction "+IN_10") (pintype "input"))
      (node (ref "IC9") (pin "11") (pinfunction "V-_11") (pintype "power_in"))
      (node (ref "IC9") (pin "12") (pinfunction "+IN_12") (pintype "input"))
      (node (ref "IC9") (pin "3") (pinfunction "+IN_3") (pintype "input"))
      (node (ref "IC9") (pin "5") (pinfunction "+IN_5") (pintype "input"))
      (node (ref "J19") (pin "1") (pinfunction "1_1") (pintype "passive"))
      (node (ref "JP1") (pin "3") (pinfunction "3_3") (pintype "passive"))
      (node (ref "JP1") (pin "5") (pinfunction "5_5") (pintype "passive"))
      (node (ref "JP1") (pin "9") (pinfunction "9_9") (pintype "passive"))
      (node (ref "JP2") (pin "1") (pinfunction "1_1") (pintype "passive"))
      (node (ref "P3") (pin "1") (pinfunction "1_1") (pintype "passive"))
      (node (ref "P3") (pin "2") (pinfunction "2_2") (pintype "passive"))
      (node (ref "P3") (pin "3") (pinfunction "3_3") (pintype "passive"))
      (node (ref "P4") (pin "1") (pinfunction "1_1") (pintype "passive"))
      (node (ref "P4") (pin "2") (pinfunction "2_2") (pintype "passive"))
      (node (ref "P4") (pin "4") (pinfunction "4_4") (pintype "passive"))
      (node (ref "Q2") (pin "E") (pinfunction "E_E") (pintype "passive"))
      (node (ref "R50") (pin "1") (pinfunction "1_1") (pintype "passive"))
      (node (ref "R59") (pin "1") (pinfunction "1_1") (pintype "passive"))
      (node (ref "R69") (pin "1") (pinfunction "1_1") (pintype "passive"))
      (node (ref "R74") (pin "1") (pinfunction "1_1") (pintype "passive"))
      (node (ref "R87") (pin "1") (pinfunction "1_1") (pintype "passive"))
      (node (ref "S2") (pin "A") (pinfunction "P_A") (pintype "passive"))
      (node (ref "S2") (pin "A'") (pinfunction "P1_A'") (pintype "passive"))
      (node (ref "U1") (pin "1") (pinfunction "GND_1") (pintype "input"))
      (node (ref "U2") (pin "1") (pinfunction "GND_1") (pintype "input"))
    )
    (net (code "78") (name "I2C_SCL") (class "Default")
      (node (ref "IC10") (pin "29") (pinfunction "PB10/SPI2_SCK/I2S_SCK/I2C2_SCL/USART3_TX_29") (pintype "bidirectional"))
      (node (ref "IC12") (pin "24") (pinfunction "SCLK_24") (pintype "bidirectional"))
      (node (ref "R52") (pin "1") (pinfunction "1_1") (pintype "passive"))
    )
    (net (code "79") (name "I2C_SDA") (class "Default")
      (node (ref "IC10") (pin "30") (pinfunction "PB11/I2C2_SDA/USART3_RX_30") (pintype "bidirectional"))
      (node (ref "IC12") (pin "23") (pinfunction "SDIN_23") (pintype "bidirectional"))
      (node (ref "R53") (pin "1") (pinfunction "1_1") (pintype "passive"))
    )
    (net (code "80") (name "I2S_LRCK") (class "Default")
      (node (ref "IC10") (pin "33") (pinfunction "PB12/SPI2_NSS/I2S2_WS/I2C2_SMBA/USART3_CK/TIM1_BKIN_33") (pintype "bidirectional"))
      (node (ref "IC12") (pin "5") (pinfunction "DACLRC_5") (pintype "bidirectional"))
      (node (ref "IC12") (pin "7") (pinfunction "ADCLRC_7") (pintype "bidirectional"))
    )
    (net (code "81") (name "I2S_MCK") (class "Default")
      (node (ref "IC10") (pin "37") (pinfunction "PC6/I2S2_MCK_37") (pintype "bidirectional"))
      (node (ref "IC12") (pin "25") (pinfunction "XTI/MCLK_25") (pintype "bidirectional"))
    )
    (net (code "82") (name "I2S_SCK") (class "Default")
      (node (ref "IC10") (pin "34") (pinfunction "PB13/SPI2_SCK/I2S2_SCK/USART3_CTS/TIM1_CH1N_34") (pintype "bidirectional"))
      (node (ref "IC12") (pin "3") (pinfunction "BCLK_3") (pintype "bidirectional"))
    )
    (net (code "83") (name "I2S_SIN") (class "Default")
      (node (ref "IC10") (pin "35") (pinfunction "PB14/SPI2_MISO/USART3_RTS/TIM1_CH2N_35") (pintype "bidirectional"))
      (node (ref "IC12") (pin "6") (pinfunction "ADCDAT_6") (pintype "bidirectional"))
    )
    (net (code "84") (name "I2S_SOUT") (class "Default")
      (node (ref "IC10") (pin "36") (pinfunction "PB15/SPI2_MOSI/I2S2_SD/TIM1_CH3N_36") (pintype "bidirectional"))
      (node (ref "IC12") (pin "4") (pinfunction "DACDAT_4") (pintype "bidirectional"))
    )
    (net (code "85") (name "JTCK") (class "Default")
      (node (ref "IC10") (pin "49") (pinfunction "PA14/JTCK-SWCLK_49") (pintype "bidirectional"))
      (node (ref "JP1") (pin "4") (pinfunction "4_4") (pintype "passive"))
    )
    (net (code "86") (name "JTDI") (class "Default")
      (node (ref "IC10") (pin "50") (pinfunction "PA15/JTDI/SPI3_NSS/I2S3_WS_50") (pintype "bidirectional"))
      (node (ref "JP1") (pin "8") (pinfunction "8_8") (pintype "passive"))
    )
    (net (code "87") (name "JTDO") (class "Default")
      (node (ref "IC10") (pin "55") (pinfunction "PB3/JTDO/SPI3_SCK/I2S3_SCK_55") (pintype "bidirectional"))
      (node (ref "JP1") (pin "6") (pinfunction "6_6") (pintype "passive"))
    )
    (net (code "88") (name "JTMS") (class "Default")
      (node (ref "IC10") (pin "46") (pinfunction "PA13/JTMS-SWDAT_46") (pintype "bidirectional"))
      (node (ref "JP1") (pin "2") (pinfunction "2_2") (pintype "passive"))
    )
    (net (code "89") (name "LED_GATE") (class "Default")
      (node (ref "IC10") (pin "38") (pinfunction "PC7/I2S3_MCK_38") (pintype "bidirectional"))
      (node (ref "R10") (pin "1") (pinfunction "1_1") (pintype "passive"))
    )
    (net (code "90") (name "LIN") (class "Default")
      (node (ref "C56") (pin "+") (pinfunction "POS_+") (pintype "passive"))
      (node (ref "IC12") (pin "20") (pinfunction "LLINEIN_20") (pintype "bidirectional"))
    )
    (net (code "91") (name "LOUT") (class "Default")
      (node (ref "C40") (pin "+") (pinfunction "POS_+") (pintype "passive"))
      (node (ref "IC12") (pin "12") (pinfunction "LOUT_12") (pintype "bidirectional"))
    )
    (net (code "92") (name "Net-(C40-NEG)") (class "Default")
      (node (ref "C40") (pin "-") (pinfunction "NEG_-") (pintype "passive"))
      (node (ref "R58") (pin "2") (pinfunction "2_2") (pintype "passive"))
      (node (ref "R59") (pin "2") (pinfunction "2_2") (pintype "passive"))
    )
    (net (code "93") (name "Net-(C52-POS)") (class "Default")
      (node (ref "C47") (pin "1") (pinfunction "1_1") (pintype "passive"))
      (node (ref "C52") (pin "+") (pinfunction "POS_+") (pintype "passive"))
      (node (ref "IC12") (pin "16") (pinfunction "VMID_16") (pintype "bidirectional"))
    )
    (net (code "94") (name "Net-(C53-NEG)") (class "Default")
      (node (ref "C53") (pin "-") (pinfunction "NEG_-") (pintype "passive"))
      (node (ref "R68") (pin "2") (pinfunction "2_2") (pintype "passive"))
      (node (ref "R69") (pin "2") (pinfunction "2_2") (pintype "passive"))
    )
    (net (code "95") (name "Net-(C55-NEG)") (class "Default")
      (node (ref "C54") (pin "1") (pinfunction "1_1") (pintype "passive"))
      (node (ref "C55") (pin "-") (pinfunction "NEG_-") (pintype "passive"))
      (node (ref "R74") (pin "2") (pinfunction "2_2") (pintype "passive"))
      (node (ref "R75") (pin "1") (pinfunction "1_1") (pintype "passive"))
    )
    (net (code "96") (name "Net-(C56-NEG)") (class "Default")
      (node (ref "C56") (pin "-") (pinfunction "NEG_-") (pintype "passive"))
      (node (ref "C57") (pin "1") (pinfunction "1_1") (pintype "passive"))
      (node (ref "R86") (pin "1") (pinfunction "1_1") (pintype "passive"))
      (node (ref "R87") (pin "2") (pinfunction "2_2") (pintype "passive"))
    )
    (net (code "97") (name "Net-(IC6A--IN)") (class "Default")
      (node (ref "C26") (pin "1") (pinfunction "1_1") (pintype "passive"))
      (node (ref "IC6") (pin "2") (pinfunction "-IN_2") (pintype "input"))
      (node (ref "R30") (pin "1") (pinfunction "1_1") (pintype "passive"))
      (node (ref "R31") (pin "1") (pinfunction "1_1") (pintype "passive"))
      (node (ref "R34") (pin "2") (pinfunction "2_2") (pintype "passive"))
    )
    (net (code "98") (name "Net-(IC6B--IN)") (class "Default")
      (node (ref "C27") (pin "1") (pinfunction "1_1") (pintype "passive"))
      (node (ref "IC6") (pin "6") (pinfunction "-IN_6") (pintype "input"))
      (node (ref "R32") (pin "1") (pinfunction "1_1") (pintype "passive"))
      (node (ref "R33") (pin "1") (pinfunction "1_1") (pintype "passive"))
      (node (ref "R35") (pin "2") (pinfunction "2_2") (pintype "passive"))
    )
    (net (code "99") (name "Net-(IC6C--IN)") (class "Default")
      (node (ref "C15") (pin "1") (pinfunction "1_1") (pintype "passive"))
      (node (ref "IC6") (pin "9") (pinfunction "-IN_9") (pintype "input"))
      (node (ref "R12") (pin "2") (pinfunction "2_2") (pintype "passive"))
      (node (ref "R15") (pin "1") (pinfunction "1_1") (pintype "passive"))
      (node (ref "R16") (pin "1") (pinfunction "1_1") (pintype "passive"))
    )
    (net (code "100") (name "Net-(IC6D--IN)") (class "Default")
      (node (ref "C14") (pin "1") (pinfunction "1_1") (pintype "passive"))
      (node (ref "IC6") (pin "13") (pinfunction "-IN_13") (pintype "input"))
      (node (ref "R11") (pin "2") (pinfunction "2_2") (pintype "passive"))
      (node (ref "R13") (pin "1") (pinfunction "1_1") (pintype "passive"))
      (node (ref "R14") (pin "1") (pinfunction "1_1") (pintype "passive"))
    )
    (net (code "101") (name "Net-(IC7A--IN)") (class "Default")
      (node (ref "C30") (pin "1") (pinfunction "1_1") (pintype "passive"))
      (node (ref "IC7") (pin "2") (pinfunction "-IN_2") (pintype "input"))
      (node (ref "R40") (pin "1") (pinfunction "1_1") (pintype "passive"))
      (node (ref "R41") (pin "1") (pinfunction "1_1") (pintype "passive"))
      (node (ref "R46") (pin "2") (pinfunction "2_2") (pintype "passive"))
    )
    (net (code "102") (name "Net-(IC7B--IN)") (class "Default")
      (node (ref "C28") (pin "1") (pinfunction "1_1") (pintype "passive"))
      (node (ref "IC7") (pin "6") (pinfunction "-IN_6") (pintype "input"))
      (node (ref "R29") (pin "2") (pinfunction "2_2") (pintype "passive"))
      (node (ref "R42") (pin "1") (pinfunction "1_1") (pintype "passive"))
      (node (ref "R43") (pin "1") (pinfunction "1_1") (pintype "passive"))
    )
    (net (code "103") (name "Net-(IC7C--IN)") (class "Default")
      (node (ref "C20") (pin "1") (pinfunction "1_1") (pintype "passive"))
      (node (ref "IC7") (pin "9") (pinfunction "-IN_9") (pintype "input"))
      (node (ref "R18") (pin "2") (pinfunction "2_2") (pintype "passive"))
      (node (ref "R21") (pin "1") (pinfunction "1_1") (pintype "passive"))
      (node (ref "R22") (pin "1") (pinfunction "1_1") (pintype "passive"))
    )
    (net (code "104") (name "Net-(IC7D--IN)") (class "Default")
      (node (ref "C19") (pin "1") (pinfunction "1_1") (pintype "passive"))
      (node (ref "IC7") (pin "13") (pinfunction "-IN_13") (pintype "input"))
      (node (ref "R17") (pin "2") (pinfunction "2_2") (pintype "passive"))
      (node (ref "R19") (pin "1") (pinfunction "1_1") (pintype "passive"))
      (node (ref "R20") (pin "1") (pinfunction "1_1") (pintype "passive"))
    )
    (net (code "105") (name "Net-(IC9A--IN)") (class "Default")
      (node (ref "C25") (pin "1") (pinfunction "1_1") (pintype "passive"))
      (node (ref "IC9") (pin "2") (pinfunction "-IN_2") (pintype "input"))
      (node (ref "R28") (pin "2") (pinfunction "2_2") (pintype "passive"))
      (node (ref "R38") (pin "1") (pinfunction "1_1") (pintype "passive"))
      (node (ref "R39") (pin "1") (pinfunction "1_1") (pintype "passive"))
    )
    (net (code "106") (name "Net-(IC9B--IN)") (class "Default")
      (node (ref "C24") (pin "1") (pinfunction "1_1") (pintype "passive"))
      (node (ref "IC9") (pin "6") (pinfunction "-IN_6") (pintype "input"))
      (node (ref "R27") (pin "2") (pinfunction "2_2") (pintype "passive"))
      (node (ref "R36") (pin "1") (pinfunction "1_1") (pintype "passive"))
      (node (ref "R37") (pin "1") (pinfunction "1_1") (pintype "passive"))
    )
    (net (code "107") (name "Net-(IC9C--IN)") (class "Default")
      (node (ref "IC9") (pin "8") (pinfunction "OUT_8") (pintype "output"))
      (node (ref "IC9") (pin "9") (pinfunction "-IN_9") (pintype "input"))
    )
    (net (code "108") (name "Net-(IC9D--IN)") (class "Default")
      (node (ref "IC9") (pin "13") (pinfunction "-IN_13") (pintype "input"))
      (node (ref "IC9") (pin "14") (pinfunction "OUT_14") (pintype "output"))
    )
    (net (code "109") (name "Net-(IC10-PA8{slash}USART1_CK{slash}TIM1_CH1{slash}MCO)") (class "Default")
      (node (ref "IC10") (pin "41") (pinfunction "PA8/USART1_CK/TIM1_CH1/MCO_41") (pintype "bidirectional"))
      (node (ref "R47") (pin "1") (pinfunction "1_1") (pintype "passive"))
    )
    (net (code "110") (name "Net-(IC10-PA11{slash}USART1_CTS{slash}CANRX{slash}USBDM{slash}TIM1_CH4)") (class "Default")
      (node (ref "IC10") (pin "44") (pinfunction "PA11/USART1_CTS/CANRX/USBDM/TIM1_CH4_44") (pintype "bidirectional"))
      (node (ref "R44") (pin "1") (pinfunction "1_1") (pintype "passive"))
    )
    (net (code "111") (name "Net-(IC10-PD0{slash}OSC_IN)") (class "Default")
      (node (ref "C12") (pin "2") (pinfunction "2_2") (pintype "passive"))
      (node (ref "IC10") (pin "5") (pinfunction "PD0/OSC_IN_5") (pintype "bidirectional"))
      (node (ref "Q1") (pin "2") (pinfunction "2_2") (pintype "passive"))
    )
    (net (code "112") (name "Net-(IC10-PD1{slash}OSC_OUT)") (class "Default")
      (node (ref "C11") (pin "2") (pinfunction "2_2") (pintype "passive"))
      (node (ref "IC10") (pin "6") (pinfunction "PD1/OSC_OUT_6") (pintype "bidirectional"))
      (node (ref "Q1") (pin "1") (pinfunction "1_1") (pintype "passive"))
    )
    (net (code "113") (name "Net-(IC10-VCAP_1)") (class "Default")
      (node (ref "C31") (pin "1") (pinfunction "1_1") (pintype "passive"))
      (node (ref "IC10") (pin "31") (pinfunction "VCAP_1_31") (pintype "power_in"))
    )
    (net (code "114") (name "Net-(IC10-VCAP_2)") (class "Default")
      (node (ref "C35") (pin "1") (pinfunction "1_1") (pintype "passive"))
      (node (ref "IC10") (pin "47") (pinfunction "VCAP_2_47") (pintype "power_in"))
    )
    (net (code "115") (name "Net-(IC13A--IN)") (class "Default")
      (node (ref "IC13") (pin "1") (pinfunction "OUT_1") (pintype "output"))
      (node (ref "IC13") (pin "2") (pinfunction "-IN_2") (pintype "input"))
    )
    (net (code "116") (name "Net-(IC13B--IN)") (class "Default")
      (node (ref "C50") (pin "1") (pinfunction "1_1") (pintype "passive"))
      (node (ref "IC13") (pin "6") (pinfunction "-IN_6") (pintype "input"))
      (node (ref "R70") (pin "1") (pinfunction "1_1") (pintype "passive"))
      (node (ref "R71") (pin "1") (pinfunction "1_1") (pintype "passive"))
      (node (ref "R73") (pin "2") (pinfunction "2_2") (pintype "passive"))
    )
    (net (code "117") (name "Net-(IC13C--IN)") (class "Default")
      (node (ref "C42") (pin "1") (pinfunction "1_1") (pintype "passive"))
      (node (ref "IC13") (pin "9") (pinfunction "-IN_9") (pintype "input"))
      (node (ref "R49") (pin "2") (pinfunction "2_2") (pintype "passive"))
      (node (ref "R56") (pin "1") (pinfunction "1_1") (pintype "passive"))
      (node (ref "R57") (pin "1") (pinfunction "1_1") (pintype "passive"))
    )
    (net (code "118") (name "Net-(IC13D--IN)") (class "Default")
      (node (ref "C41") (pin "1") (pinfunction "1_1") (pintype "passive"))
      (node (ref "IC13") (pin "13") (pinfunction "-IN_13") (pintype "input"))
      (node (ref "R48") (pin "2") (pinfunction "2_2") (pintype "passive"))
      (node (ref "R54") (pin "1") (pinfunction "1_1") (pintype "passive"))
      (node (ref "R55") (pin "1") (pinfunction "1_1") (pintype "passive"))
    )
    (net (code "119") (name "Net-(IC14A--IN)") (class "Default")
      (node (ref "C49") (pin "1") (pinfunction "1_1") (pintype "passive"))
      (node (ref "IC14") (pin "2") (pinfunction "-IN_2") (pintype "input"))
      (node (ref "R68") (pin "1") (pinfunction "1_1") (pintype "passive"))
      (node (ref "R72") (pin "2") (pinfunction "2_2") (pintype "passive"))
    )
    (net (code "120") (name "Net-(IC14A-OUT)") (class "Default")
      (node (ref "C49") (pin "2") (pinfunction "2_2") (pintype "passive"))
      (node (ref "IC14") (pin "1") (pinfunction "OUT_1") (pintype "output"))
      (node (ref "R72") (pin "1") (pinfunction "1_1") (pintype "passive"))
      (node (ref "R89") (pin "2") (pinfunction "2_2") (pintype "passive"))
    )
    (net (code "121") (name "Net-(IC14B--IN)") (class "Default")
      (node (ref "C43") (pin "1") (pinfunction "1_1") (pintype "passive"))
      (node (ref "IC14") (pin "6") (pinfunction "-IN_6") (pintype "input"))
      (node (ref "R51") (pin "2") (pinfunction "2_2") (pintype "passive"))
      (node (ref "R58") (pin "1") (pinfunction "1_1") (pintype "passive"))
    )
    (net (code "122") (name "Net-(IC14B-OUT)") (class "Default")
      (node (ref "C43") (pin "2") (pinfunction "2_2") (pintype "passive"))
      (node (ref "IC14") (pin "7") (pinfunction "OUT_7") (pintype "output"))
      (node (ref "R51") (pin "1") (pinfunction "1_1") (pintype "passive"))
      (node (ref "R88") (pin "2") (pinfunction "2_2") (pintype "passive"))
    )
    (net (code "123") (name "Net-(Q2-PadB)") (class "Default")
      (node (ref "Q2") (pin "B") (pinfunction "B_B") (pintype "passive"))
      (node (ref "R67") (pin "2") (pinfunction "2_2") (pintype "passive"))
    )
    (net (code "124") (name "Net-(U1-IN)") (class "Default")
      (node (ref "C5") (pin "1") (pinfunction "1_1") (pintype "passive"))
      (node (ref "L1") (pin "2") (pinfunction "2_2") (pintype "passive"))
      (node (ref "U1") (pin "3") (pinfunction "IN_3") (pintype "input"))
    )
    (net (code "125") (name "Net-(U2-IN)") (class "Default")
      (node (ref "C4") (pin "1") (pinfunction "1_1") (pintype "passive"))
      (node (ref "L2") (pin "2") (pinfunction "2_2") (pintype "passive"))
      (node (ref "U2") (pin "3") (pinfunction "IN_3") (pintype "input"))
    )
    (net (code "126") (name "RESET") (class "Default")
      (node (ref "IC10") (pin "7") (pinfunction "NRST_7") (pintype "bidirectional"))
      (node (ref "JP1") (pin "10") (pinfunction "10_10") (pintype "passive"))
      (node (ref "R45") (pin "1") (pinfunction "1_1") (pintype "passive"))
      (node (ref "S2") (pin "B") (pinfunction "S_B") (pintype "passive"))
      (node (ref "S2") (pin "B'") (pinfunction "S1_B'") (pintype "passive"))
    )
    (net (code "127") (name "RIN") (class "Default")
      (node (ref "C55") (pin "+") (pinfunction "POS_+") (pintype "passive"))
      (node (ref "IC12") (pin "19") (pinfunction "RLINEIN_19") (pintype "bidirectional"))
    )
    (net (code "128") (name "ROUT") (class "Default")
      (node (ref "C53") (pin "+") (pinfunction "POS_+") (pintype "passive"))
      (node (ref "IC12") (pin "13") (pinfunction "ROUT_13") (pintype "bidirectional"))
    )
    (net (code "129") (name "RX") (class "Default")
      (node (ref "IC10") (pin "43") (pinfunction "PA10/USART1_RX/TIM1_CH3_43") (pintype "bidirectional"))
      (node (ref "JP2") (pin "4") (pinfunction "4_4") (pintype "passive"))
    )
    (net (code "130") (name "TX") (class "Default")
      (node (ref "IC10") (pin "42") (pinfunction "PA9/USART1_TX/TIM1_CH2_42") (pintype "bidirectional"))
      (node (ref "JP2") (pin "5") (pinfunction "5_5") (pintype "passive"))
    )
    (net (code "131") (name "VBAT") (class "Default")
      (node (ref "IC10") (pin "1") (pinfunction "VBAT_1") (pintype "power_in"))
    )
    (net (code "132") (name "VCC") (class "Default")
      (node (ref "C3") (pin "+") (pinfunction "POS_+") (pintype "passive"))
      (node (ref "C44") (pin "1") (pinfunction "1_1") (pintype "passive"))
      (node (ref "IC14") (pin "8") (pinfunction "V+_8") (pintype "power_in"))
      (node (ref "J19") (pin "3") (pinfunction "3_3") (pintype "passive"))
    )
    (net (code "133") (name "VEE") (class "Default")
      (node (ref "C1") (pin "-") (pinfunction "NEG_-") (pintype "passive"))
      (node (ref "C45") (pin "2") (pinfunction "2_2") (pintype "passive"))
      (node (ref "IC14") (pin "4") (pinfunction "V-_4") (pintype "power_in"))
      (node (ref "J19") (pin "2") (pinfunction "2_2") (pintype "passive"))
      (node (ref "R1") (pin "1") (pinfunction "1_1") (pintype "passive"))
      (node (ref "R2") (pin "1") (pinfunction "1_1") (pintype "passive"))
    )
    (net (code "134") (name "unconnected-(IC10-PA12{slash}USART1_RTS{slash}CANTX{slash}USBDP{slash}TIM1_ETR-Pad45)") (class "Default")
      (node (ref "IC10") (pin "45") (pinfunction "PA12/USART1_RTS/CANTX/USBDP/TIM1_ETR_45") (pintype "bidirectional"))
    )
    (net (code "135") (name "unconnected-(IC10-PB4{slash}NJTRST{slash}SPI3_MISO{slash}SPI1_MISO-Pad56)") (class "Default")
      (node (ref "IC10") (pin "56") (pinfunction "PB4/NJTRST/SPI3_MISO/SPI1_MISO_56") (pintype "bidirectional"))
    )
    (net (code "136") (name "unconnected-(IC10-PB9{slash}SPI2_NSS{slash}I2S2_WS{slash}I2C1_SDA{slash}TIM4_CH4-Pad62)") (class "Default")
      (node (ref "IC10") (pin "62") (pinfunction "PB9/SPI2_NSS/I2S2_WS/I2C1_SDA/TIM4_CH4_62") (pintype "bidirectional"))
    )
    (net (code "137") (name "unconnected-(IC10-PC8-Pad39)") (class "Default")
      (node (ref "IC10") (pin "39") (pinfunction "PC8_39") (pintype "bidirectional"))
    )
    (net (code "138") (name "unconnected-(IC10-PC9{slash}I2S2_CKIN{slash}I2S3_CKIN-Pad40)") (class "Default")
      (node (ref "IC10") (pin "40") (pinfunction "PC9/I2S2_CKIN/I2S3_CKIN_40") (pintype "bidirectional"))
    )
    (net (code "139") (name "unconnected-(IC10-PC10{slash}SPI3_SCK{slash}I2S3_SCK{slash}UART4_TX-Pad51)") (class "Default")
      (node (ref "IC10") (pin "51") (pinfunction "PC10/SPI3_SCK/I2S3_SCK/UART4_TX_51") (pintype "bidirectional"))
    )
    (net (code "140") (name "unconnected-(IC10-PC11{slash}UART4_RX{slash}SPI3_MISO{slash}USART3_RX-Pad52)") (class "Default")
      (node (ref "IC10") (pin "52") (pinfunction "PC11/UART4_RX/SPI3_MISO/USART3_RX_52") (pintype "bidirectional"))
    )
    (net (code "141") (name "unconnected-(IC10-PC12{slash}UART5_TX{slash}I2S3_SD{slash}USART3_CK-Pad53)") (class "Default")
      (node (ref "IC10") (pin "53") (pinfunction "PC12/UART5_TX/I2S3_SD/USART3_CK_53") (pintype "bidirectional"))
    )
    (net (code "142") (name "unconnected-(IC10-PD2{slash}TIM3-ETR-Pad54)") (class "Default")
      (node (ref "IC10") (pin "54") (pinfunction "PD2/TIM3-ETR_54") (pintype "bidirectional"))
    )
    (net (code "143") (name "unconnected-(IC12-CLKOUT-Pad2)") (class "Default")
      (node (ref "IC12") (pin "2") (pinfunction "CLKOUT_2") (pintype "bidirectional"))
    )
    (net (code "144") (name "unconnected-(IC12-LHPOUT-Pad9)") (class "Default")
      (node (ref "IC12") (pin "9") (pinfunction "LHPOUT_9") (pintype "bidirectional"))
    )
    (net (code "145") (name "unconnected-(IC12-MICBIAS-Pad17)") (class "Default")
      (node (ref "IC12") (pin "17") (pinfunction "MICBIAS_17") (pintype "bidirectional"))
    )
    (net (code "146") (name "unconnected-(IC12-MICIN-Pad18)") (class "Default")
      (node (ref "IC12") (pin "18") (pinfunction "MICIN_18") (pintype "bidirectional"))
    )
    (net (code "147") (name "unconnected-(IC12-RHPOUT-Pad10)") (class "Default")
      (node (ref "IC12") (pin "10") (pinfunction "RHPOUT_10") (pintype "bidirectional"))
    )
    (net (code "148") (name "unconnected-(IC12-XTO-Pad26)") (class "Default")
      (node (ref "IC12") (pin "26") (pinfunction "XTO_26") (pintype "bidirectional"))
    )
    (net (code "149") (name "unconnected-(J19-Pad4)") (class "Default")
      (node (ref "J19") (pin "4") (pinfunction "4_4") (pintype "passive"))
    )
    (net (code "150") (name "unconnected-(J19-Pad6)") (class "Default")
      (node (ref "J19") (pin "6") (pinfunction "6_6") (pintype "passive"))
    )
    (net (code "151") (name "unconnected-(JP1-Pad7)") (class "Default")
      (node (ref "JP1") (pin "7") (pinfunction "7_7") (pintype "passive"))
    )
    (net (code "152") (name "unconnected-(JP2-Pad2)") (class "Default")
      (node (ref "JP2") (pin "2") (pinfunction "2_2") (pintype "passive"))
    )
    (net (code "153") (name "unconnected-(JP2-Pad3)") (class "Default")
      (node (ref "JP2") (pin "3") (pinfunction "3_3") (pintype "passive"))
    )
    (net (code "154") (name "unconnected-(JP2-Pad6)") (class "Default")
      (node (ref "JP2") (pin "6") (pinfunction "6_6") (pintype "passive"))
    )
    (net (code "155") (name "unconnected-(P6-Pad3)") (class "Default")
      (node (ref "P6") (pin "3") (pinfunction "3_3") (pintype "passive"))
    )
  )
)
